# Testing_FixtureForAICarBoard.net
KiCad netlist of a schematic drawn in EAGLE
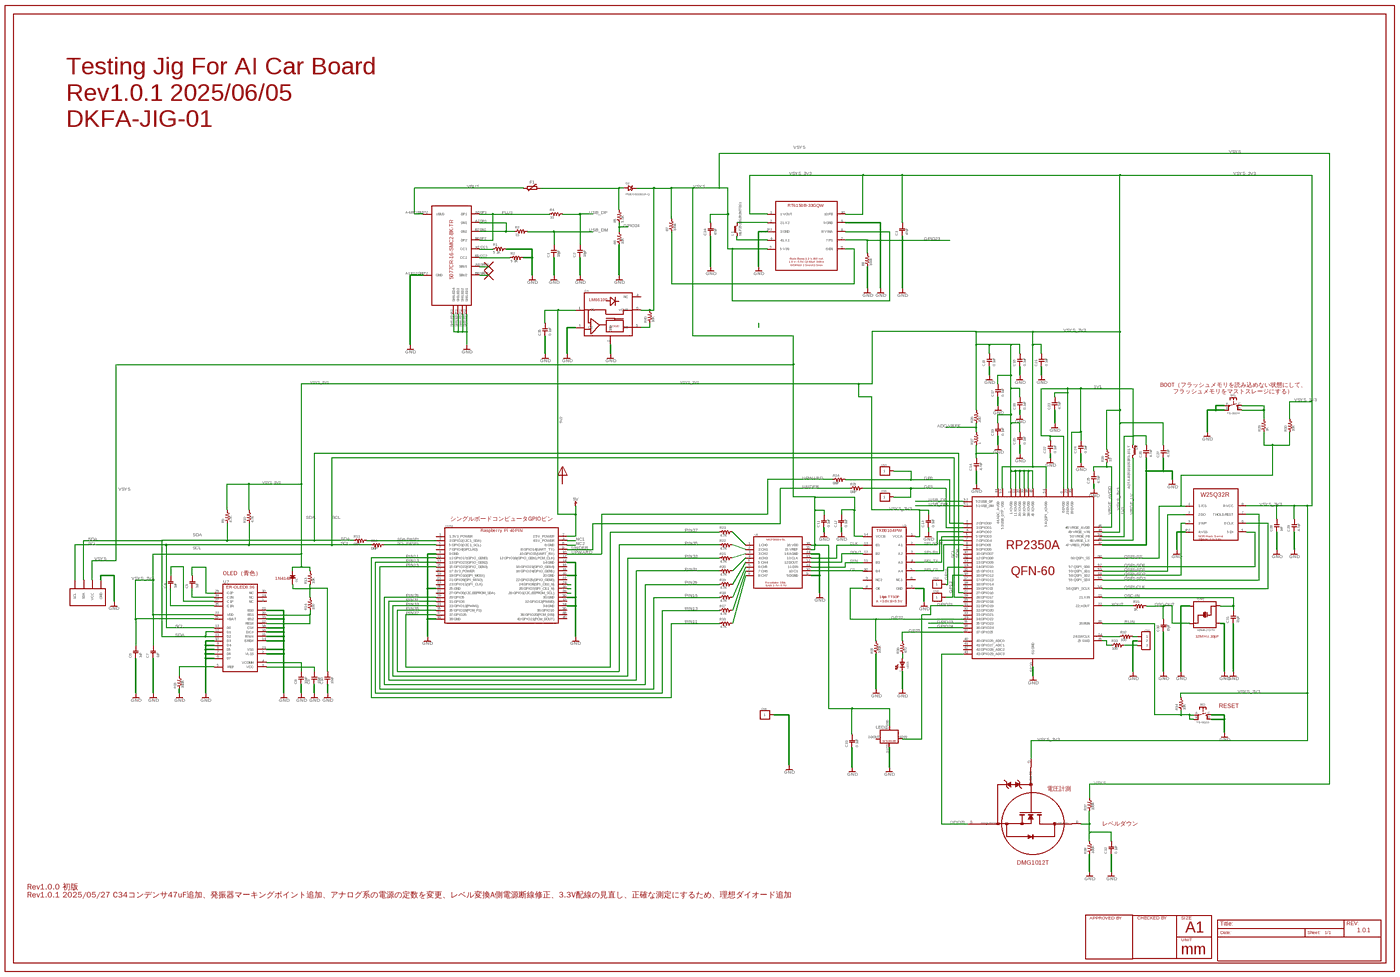
[diagram p0: schematic, sheet 1, overview]
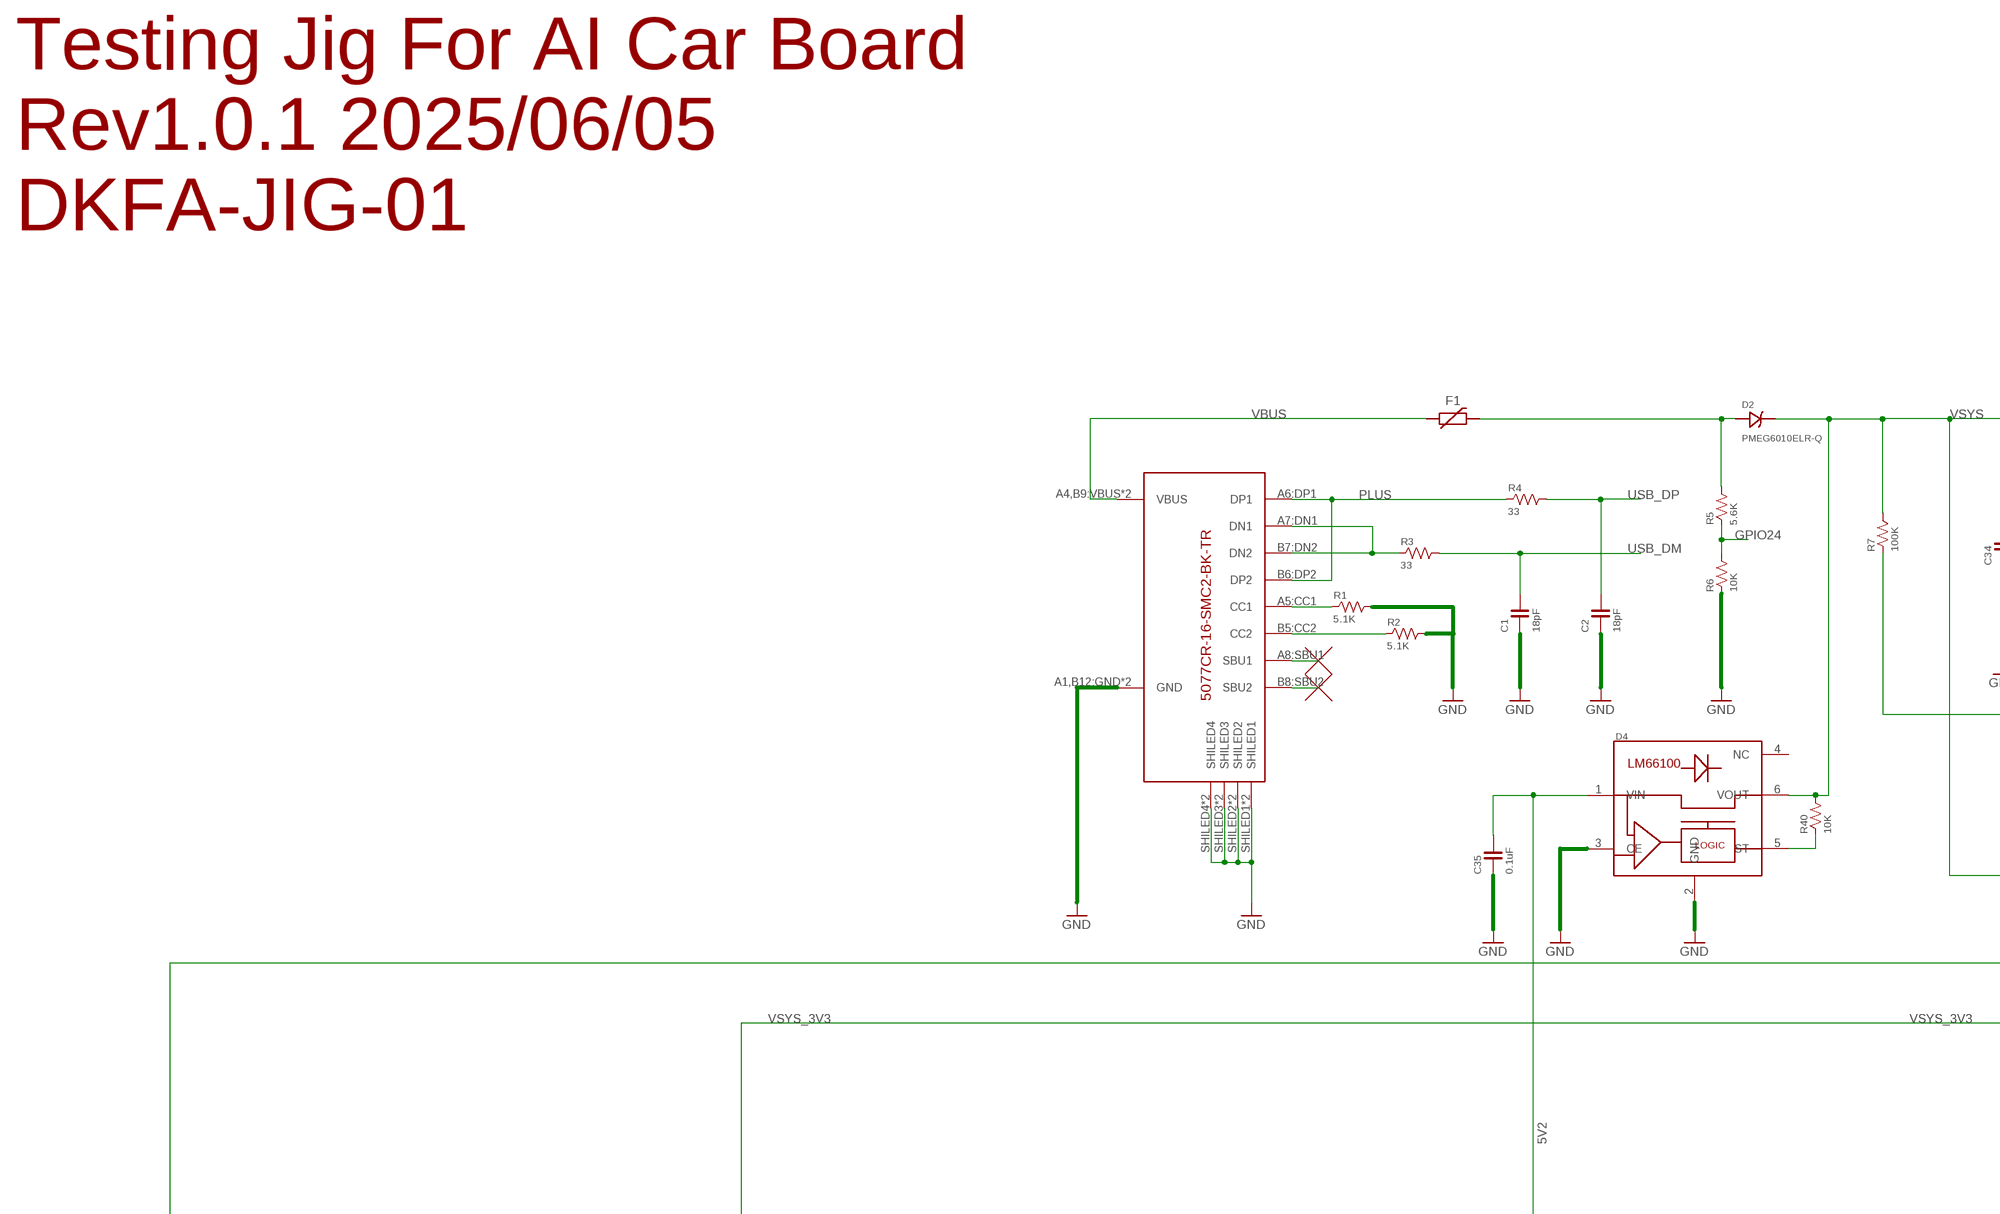
[diagram p1: schematic, sheet 1, part 1 of 4]
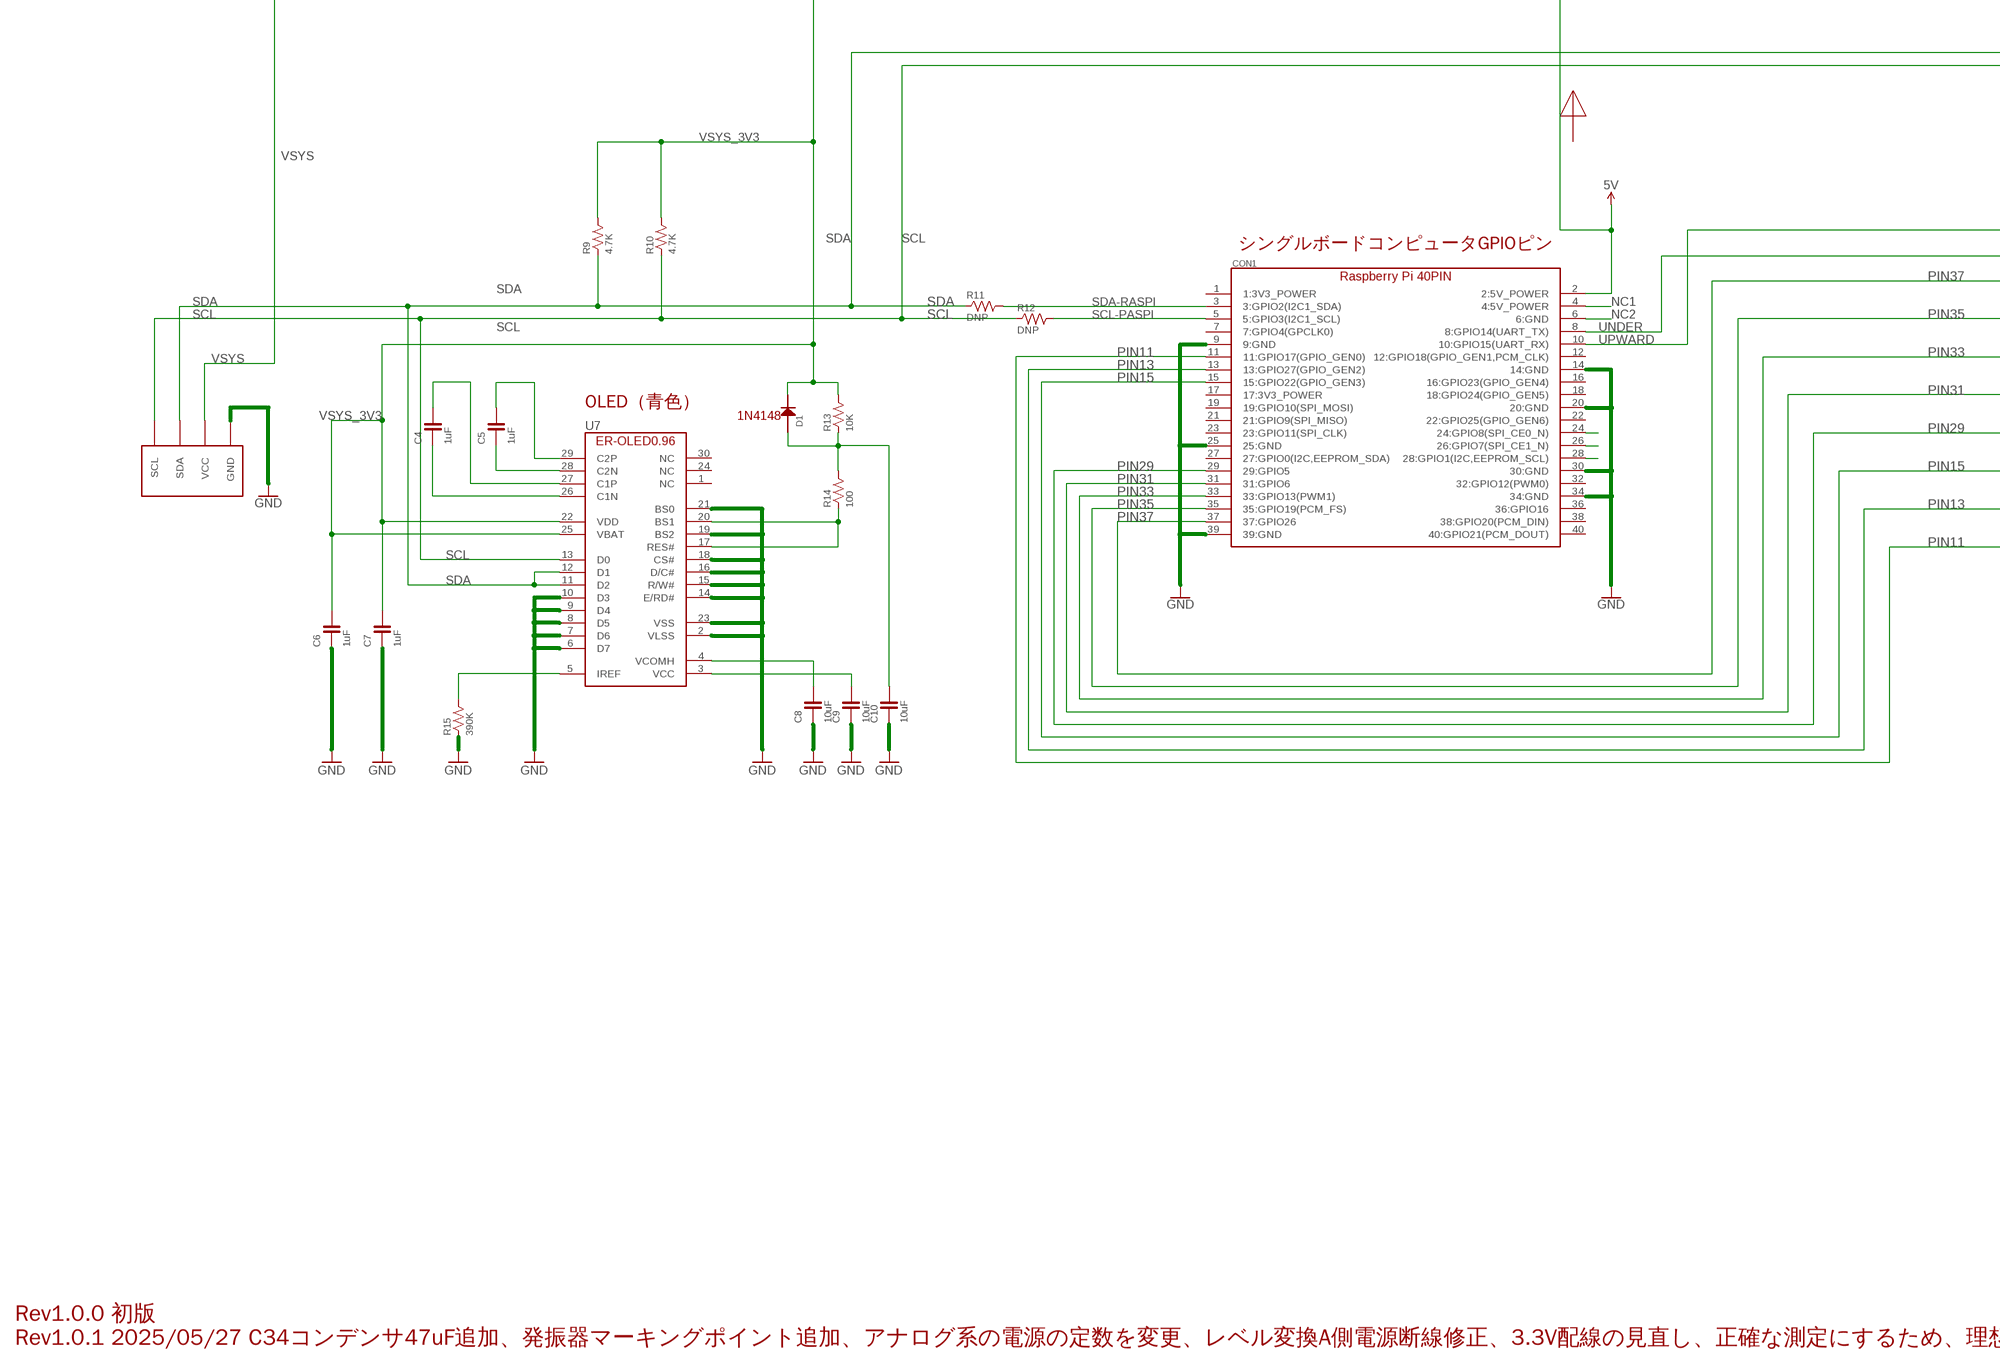
[diagram p2: schematic, sheet 1, part 2 of 4]
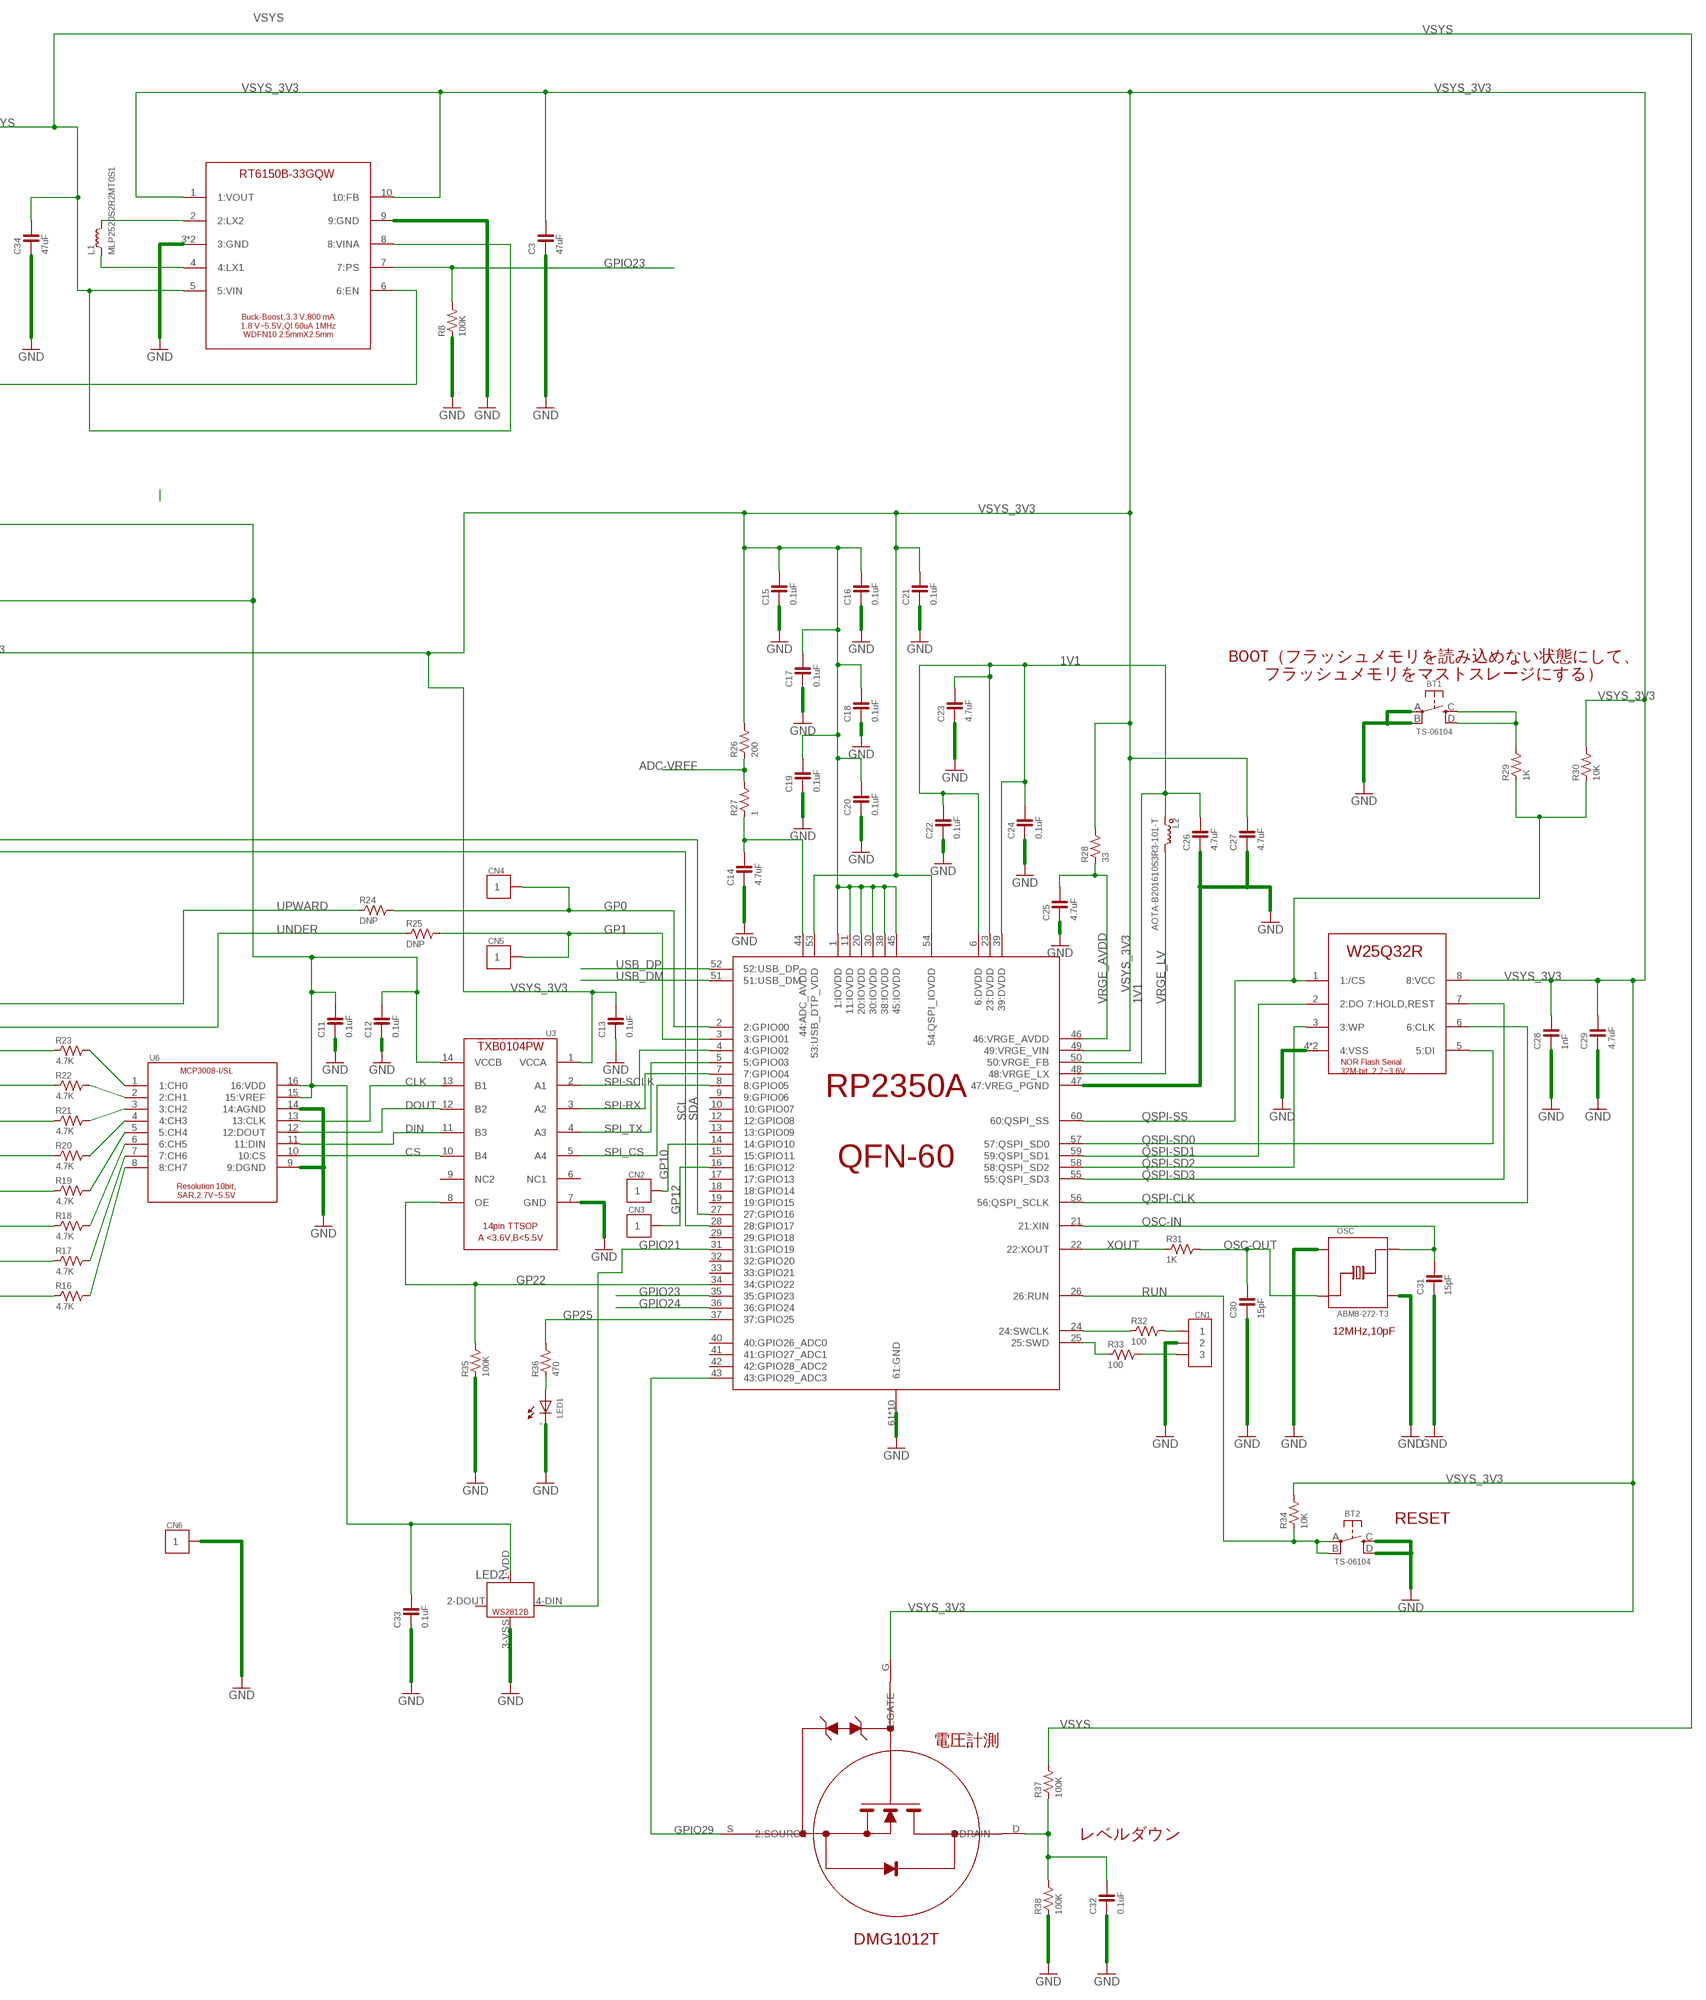
[diagram p3: schematic, sheet 1, part 3 of 4]
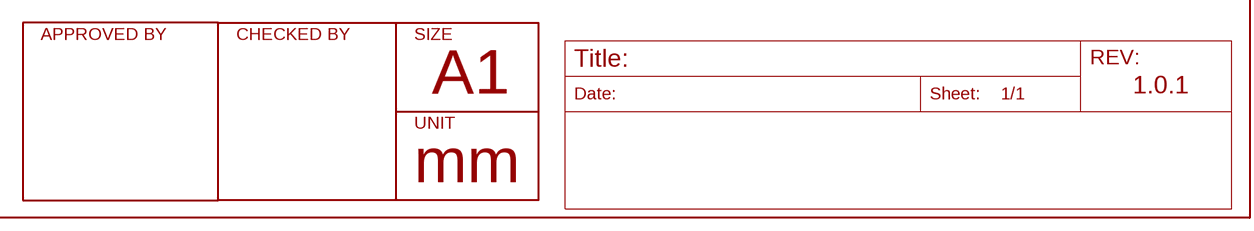
[diagram p4: schematic, sheet 1, part 4 of 4]

(export (version "E")
  (design (tool "Eeschema 10.0.6"))
  (components
    (comp (ref "BT1")
      (value "TS-06104")
      (footprint "eagle-import:TS-06104")
      (libsource (lib "eagle-import") (part "TS-06104"))
    )
    (comp (ref "BT2")
      (value "TS-06104")
      (footprint "eagle-import:TS-06104")
      (libsource (lib "eagle-import") (part "TS-06104"))
    )
    (comp (ref "C1")
      (value "18pF")
      (footprint "eagle-import:0603-BOTTOM")
      (fields (field (name "SPICEPREFIX") "C"))
      (libsource (lib "eagle-import") (part "CAPACITOR-0603-BOTTOM"))
    )
    (comp (ref "C2")
      (value "18pF")
      (footprint "eagle-import:0603-BOTTOM")
      (fields (field (name "SPICEPREFIX") "C"))
      (libsource (lib "eagle-import") (part "CAPACITOR-0603-BOTTOM"))
    )
    (comp (ref "C3")
      (value "47uF")
      (footprint "eagle-import:0603-BOTTOM")
      (fields (field (name "SPICEPREFIX") "C"))
      (libsource (lib "eagle-import") (part "CAPACITOR-0603-BOTTOM"))
    )
    (comp (ref "C4")
      (value "1uF")
      (footprint "eagle-import:0603-BOTTOM")
      (libsource (lib "eagle-import") (part "CAPACITOR-0603-BOTTOM"))
    )
    (comp (ref "C5")
      (value "1uF")
      (footprint "eagle-import:0603-BOTTOM")
      (libsource (lib "eagle-import") (part "CAPACITOR-0603-BOTTOM"))
    )
    (comp (ref "C6")
      (value "1uF")
      (footprint "eagle-import:0603-BOTTOM")
      (libsource (lib "eagle-import") (part "CAPACITOR-0603-BOTTOM"))
    )
    (comp (ref "C7")
      (value "1uF")
      (footprint "eagle-import:0603-BOTTOM")
      (libsource (lib "eagle-import") (part "CAPACITOR-0603-BOTTOM"))
    )
    (comp (ref "C8")
      (value "10uF")
      (footprint "eagle-import:0603-BOTTOM")
      (libsource (lib "eagle-import") (part "CAPACITOR-0603-BOTTOM"))
    )
    (comp (ref "C9")
      (value "10uF")
      (footprint "eagle-import:0603-BOTTOM")
      (libsource (lib "eagle-import") (part "CAPACITOR-0603-BOTTOM"))
    )
    (comp (ref "C10")
      (value "10uF")
      (footprint "eagle-import:0603-BOTTOM")
      (libsource (lib "eagle-import") (part "CAPACITOR-0603-BOTTOM"))
    )
    (comp (ref "C11")
      (value "0.1uF")
      (footprint "eagle-import:0603-BOTTOM")
      (fields (field (name "SPICEPREFIX") "C"))
      (libsource (lib "eagle-import") (part "CAPACITOR-0603-BOTTOM"))
    )
    (comp (ref "C12")
      (value "0.1uF")
      (footprint "eagle-import:0603-BOTTOM")
      (fields (field (name "SPICEPREFIX") "C"))
      (libsource (lib "eagle-import") (part "CAPACITOR-0603-BOTTOM"))
    )
    (comp (ref "C13")
      (value "0.1uF")
      (footprint "eagle-import:0603-BOTTOM")
      (fields (field (name "SPICEPREFIX") "C"))
      (libsource (lib "eagle-import") (part "CAPACITOR-0603-BOTTOM"))
    )
    (comp (ref "C14")
      (value "4.7uF")
      (footprint "eagle-import:0603-BOTTOM")
      (fields (field (name "SPICEPREFIX") "C"))
      (libsource (lib "eagle-import") (part "CAPACITOR-0603-BOTTOM"))
    )
    (comp (ref "C15")
      (value "0.1uF")
      (footprint "eagle-import:0603-BOTTOM")
      (fields (field (name "SPICEPREFIX") "C"))
      (libsource (lib "eagle-import") (part "CAPACITOR-0603-BOTTOM"))
    )
    (comp (ref "C16")
      (value "0.1uF")
      (footprint "eagle-import:0603-BOTTOM")
      (fields (field (name "SPICEPREFIX") "C"))
      (libsource (lib "eagle-import") (part "CAPACITOR-0603-BOTTOM"))
    )
    (comp (ref "C17")
      (value "0.1uF")
      (footprint "eagle-import:0603-BOTTOM")
      (fields (field (name "SPICEPREFIX") "C"))
      (libsource (lib "eagle-import") (part "CAPACITOR-0603-BOTTOM"))
    )
    (comp (ref "C18")
      (value "0.1uF")
      (footprint "eagle-import:0603-BOTTOM")
      (fields (field (name "SPICEPREFIX") "C"))
      (libsource (lib "eagle-import") (part "CAPACITOR-0603-BOTTOM"))
    )
    (comp (ref "C19")
      (value "0.1uF")
      (footprint "eagle-import:0603-BOTTOM")
      (fields (field (name "SPICEPREFIX") "C"))
      (libsource (lib "eagle-import") (part "CAPACITOR-0603-BOTTOM"))
    )
    (comp (ref "C20")
      (value "0.1uF")
      (footprint "eagle-import:0603-BOTTOM")
      (fields (field (name "SPICEPREFIX") "C"))
      (libsource (lib "eagle-import") (part "CAPACITOR-0603-BOTTOM"))
    )
    (comp (ref "C21")
      (value "0.1uF")
      (footprint "eagle-import:0603-BOTTOM")
      (fields (field (name "SPICEPREFIX") "C"))
      (libsource (lib "eagle-import") (part "CAPACITOR-0603-BOTTOM"))
    )
    (comp (ref "C22")
      (value "0.1uF")
      (footprint "eagle-import:0603-BOTTOM")
      (fields (field (name "SPICEPREFIX") "C"))
      (libsource (lib "eagle-import") (part "CAPACITOR-0603-BOTTOM"))
    )
    (comp (ref "C23")
      (value "4.7uF")
      (footprint "eagle-import:0603-BOTTOM")
      (fields (field (name "SPICEPREFIX") "C"))
      (libsource (lib "eagle-import") (part "CAPACITOR-0603-BOTTOM"))
    )
    (comp (ref "C24")
      (value "0.1uF")
      (footprint "eagle-import:0603-BOTTOM")
      (fields (field (name "SPICEPREFIX") "C"))
      (libsource (lib "eagle-import") (part "CAPACITOR-0603-BOTTOM"))
    )
    (comp (ref "C25")
      (value "4.7uF")
      (footprint "eagle-import:0603-BOTTOM")
      (fields (field (name "SPICEPREFIX") "C"))
      (libsource (lib "eagle-import") (part "CAPACITOR-0603-BOTTOM"))
    )
    (comp (ref "C26")
      (value "4.7uF")
      (footprint "eagle-import:0603-BOTTOM")
      (fields (field (name "SPICEPREFIX") "C"))
      (libsource (lib "eagle-import") (part "CAPACITOR-0603-BOTTOM"))
    )
    (comp (ref "C27")
      (value "4.7uF")
      (footprint "eagle-import:0603-BOTTOM")
      (fields (field (name "SPICEPREFIX") "C"))
      (libsource (lib "eagle-import") (part "CAPACITOR-0603-BOTTOM"))
    )
    (comp (ref "C28")
      (value "1nF")
      (footprint "eagle-import:0603-BOTTOM")
      (fields (field (name "SPICEPREFIX") "C"))
      (libsource (lib "eagle-import") (part "CAPACITOR-0603-BOTTOM"))
    )
    (comp (ref "C29")
      (value "4.7uF")
      (footprint "eagle-import:0603-BOTTOM")
      (fields (field (name "SPICEPREFIX") "C"))
      (libsource (lib "eagle-import") (part "CAPACITOR-0603-BOTTOM"))
    )
    (comp (ref "C30")
      (value "15pF")
      (footprint "eagle-import:0603-BOTTOM")
      (fields (field (name "SPICEPREFIX") "C"))
      (libsource (lib "eagle-import") (part "CAPACITOR-0603-BOTTOM"))
    )
    (comp (ref "C31")
      (value "15pF")
      (footprint "eagle-import:0603-BOTTOM")
      (fields (field (name "SPICEPREFIX") "C"))
      (libsource (lib "eagle-import") (part "CAPACITOR-0603-BOTTOM"))
    )
    (comp (ref "C32")
      (value "0.1uF")
      (footprint "eagle-import:0603-BOTTOM")
      (fields (field (name "SPICEPREFIX") "C"))
      (libsource (lib "eagle-import") (part "CAPACITOR-0603-BOTTOM"))
    )
    (comp (ref "C33")
      (value "0.1uF")
      (footprint "eagle-import:0603-BOTTOM")
      (fields (field (name "SPICEPREFIX") "C"))
      (libsource (lib "eagle-import") (part "CAPACITOR-0603-BOTTOM"))
    )
    (comp (ref "C34")
      (value "47uF")
      (footprint "eagle-import:0603-BOTTOM")
      (fields (field (name "SPICEPREFIX") "C"))
      (libsource (lib "eagle-import") (part "CAPACITOR-0603-BOTTOM"))
    )
    (comp (ref "C35")
      (value "0.1uF")
      (footprint "eagle-import:0603-BOTTOM")
      (fields (field (name "SPICEPREFIX") "C"))
      (libsource (lib "eagle-import") (part "CAPACITOR-0603-BOTTOM"))
    )
    (comp (ref "CN1")
      (value "PIN_1X3")
      (footprint "eagle-import:PIN_1X3")
      (libsource (lib "eagle-import") (part "PIN_1X3"))
    )
    (comp (ref "CN2")
      (value "PIN_1X1-SMALL")
      (footprint "eagle-import:PIN_1X1_SMALL")
      (libsource (lib "eagle-import") (part "PIN_1X1-SMALL"))
    )
    (comp (ref "CN3")
      (value "PIN_1X1-SMALL")
      (footprint "eagle-import:PIN_1X1_SMALL")
      (libsource (lib "eagle-import") (part "PIN_1X1-SMALL"))
    )
    (comp (ref "CN4")
      (value "PIN_1X1-SMALL")
      (footprint "eagle-import:PIN_1X1_SMALL")
      (libsource (lib "eagle-import") (part "PIN_1X1-SMALL"))
    )
    (comp (ref "CN5")
      (value "PIN_1X1-SMALL")
      (footprint "eagle-import:PIN_1X1_SMALL")
      (libsource (lib "eagle-import") (part "PIN_1X1-SMALL"))
    )
    (comp (ref "CN6")
      (value "PIN_1X1-SMALL")
      (footprint "eagle-import:PIN_1X1_SMALL")
      (libsource (lib "eagle-import") (part "PIN_1X1-SMALL"))
    )
    (comp (ref "CON1")
      (value "RASPBERRYPI_SHEILD")
      (footprint "eagle-import:RASPBERRY_PI_SHILED")
      (libsource (lib "eagle-import") (part "RASPBERRYPI_SHEILD"))
    )
    (comp (ref "CON2")
      (value "5077CR-16-SMC2-BK-TR")
      (footprint "eagle-import:5077CR-16-SMC2-BK-TR")
      (fields (field (name "SPICEPREFIX") "X"))
      (libsource (lib "eagle-import") (part "5077CR-16-SMC2-BK-TR"))
    )
    (comp (ref "CON3")
      (value "FABO_BRICK_I2C-S04B-PASK-2")
      (footprint "eagle-import:FABO_BRICK_I2C_S04B-PASK-2")
      (libsource (lib "eagle-import") (part "FABO_BRICK_I2C-S04B-PASK-2"))
    )
    (comp (ref "D1")
      (value "1N4148")
      (footprint "eagle-import:1N4148W")
      (libsource (lib "eagle-import") (part "1N4148"))
    )
    (comp (ref "D2")
      (value "PMEG6010ELR-Q")
      (footprint "eagle-import:SOD123W")
      (libsource (lib "eagle-import") (part "PMEG6010ELR-Q"))
    )
    (comp (ref "D4")
      (value "LM66100")
      (footprint "eagle-import:SC-70")
      (libsource (lib "eagle-import") (part "LM66100"))
    )
    (comp (ref "F1")
      (value "POLYSWITCH1206")
      (footprint "eagle-import:1206")
      (libsource (lib "eagle-import") (part "POLYSWITCH1206"))
    )
    (comp (ref "L1")
      (value "MLP2520S2R2MT0S1")
      (footprint "eagle-import:1008(2520MM)")
      (libsource (lib "eagle-import") (part "MLP2520S2R2MT0S1"))
    )
    (comp (ref "L2")
      (value "AOTA-B201610S3R3-101-T")
      (footprint "eagle-import:0806(2016MM)")
      (libsource (lib "eagle-import") (part "AOTA-B201610S3R3-101-T"))
    )
    (comp (ref "LED1")
      (value "LED-0603")
      (footprint "eagle-import:0603")
      (libsource (lib "eagle-import") (part "LED-0603"))
    )
    (comp (ref "LED2")
      (value "WS2812B_NARROW")
      (footprint "eagle-import:WS2812B_NARROW")
      (libsource (lib "eagle-import") (part "WS2812B_NARROW"))
    )
    (comp (ref "OSC")
      (value "ABM8-272-T3")
      (footprint "eagle-import:ABM8-272-T3")
      (libsource (lib "eagle-import") (part "ABM8-272-T3"))
    )
    (comp (ref "R1")
      (value "5.1K")
      (footprint "eagle-import:0603-BOTTOM")
      (fields (field (name "SPICEPREFIX") "R"))
      (libsource (lib "eagle-import") (part "RESISTOR-0603-BOTTOM"))
    )
    (comp (ref "R2")
      (value "5.1K")
      (footprint "eagle-import:0603-BOTTOM")
      (fields (field (name "SPICEPREFIX") "R"))
      (libsource (lib "eagle-import") (part "RESISTOR-0603-BOTTOM"))
    )
    (comp (ref "R3")
      (value "33")
      (footprint "eagle-import:0603-BOTTOM")
      (fields (field (name "SPICEPREFIX") "R"))
      (libsource (lib "eagle-import") (part "RESISTOR-0603-BOTTOM"))
    )
    (comp (ref "R4")
      (value "33")
      (footprint "eagle-import:0603-BOTTOM")
      (fields (field (name "SPICEPREFIX") "R"))
      (libsource (lib "eagle-import") (part "RESISTOR-0603-BOTTOM"))
    )
    (comp (ref "R5")
      (value "5.6K")
      (footprint "eagle-import:0603")
      (libsource (lib "eagle-import") (part "RESISTOR-0603"))
    )
    (comp (ref "R6")
      (value "10K")
      (footprint "eagle-import:0603")
      (libsource (lib "eagle-import") (part "RESISTOR-0603"))
    )
    (comp (ref "R7")
      (value "100K")
      (footprint "eagle-import:0603-BOTTOM")
      (fields (field (name "SPICEPREFIX") "R"))
      (libsource (lib "eagle-import") (part "RESISTOR-0603-BOTTOM"))
    )
    (comp (ref "R8")
      (value "100K")
      (footprint "eagle-import:0603-BOTTOM")
      (fields (field (name "SPICEPREFIX") "R"))
      (libsource (lib "eagle-import") (part "RESISTOR-0603-BOTTOM"))
    )
    (comp (ref "R9")
      (value "4.7K")
      (footprint "eagle-import:0603-BOTTOM")
      (libsource (lib "eagle-import") (part "RESISTOR-0603-BOTTOM"))
    )
    (comp (ref "R10")
      (value "4.7K")
      (footprint "eagle-import:0603-BOTTOM")
      (libsource (lib "eagle-import") (part "RESISTOR-0603-BOTTOM"))
    )
    (comp (ref "R11")
      (value "DNP")
      (footprint "eagle-import:0603-BOTTOM")
      (fields (field (name "SPICEPREFIX") "R"))
      (libsource (lib "eagle-import") (part "RESISTOR-0603-BOTTOM"))
    )
    (comp (ref "R12")
      (value "DNP")
      (footprint "eagle-import:0603-BOTTOM")
      (fields (field (name "SPICEPREFIX") "R"))
      (libsource (lib "eagle-import") (part "RESISTOR-0603-BOTTOM"))
    )
    (comp (ref "R13")
      (value "10K")
      (footprint "eagle-import:0603-BOTTOM")
      (libsource (lib "eagle-import") (part "RESISTOR-0603-BOTTOM"))
    )
    (comp (ref "R14")
      (value "100")
      (footprint "eagle-import:0603-BOTTOM")
      (libsource (lib "eagle-import") (part "RESISTOR-0603-BOTTOM"))
    )
    (comp (ref "R15")
      (value "390K")
      (footprint "eagle-import:0603-BOTTOM")
      (libsource (lib "eagle-import") (part "RESISTOR-0603-BOTTOM"))
    )
    (comp (ref "R16")
      (value "4.7K")
      (footprint "eagle-import:0603-BOTTOM")
      (fields (field (name "SPICEPREFIX") "R"))
      (libsource (lib "eagle-import") (part "RESISTOR-0603-BOTTOM"))
    )
    (comp (ref "R17")
      (value "4.7K")
      (footprint "eagle-import:0603-BOTTOM")
      (fields (field (name "SPICEPREFIX") "R"))
      (libsource (lib "eagle-import") (part "RESISTOR-0603-BOTTOM"))
    )
    (comp (ref "R18")
      (value "4.7K")
      (footprint "eagle-import:0603-BOTTOM")
      (fields (field (name "SPICEPREFIX") "R"))
      (libsource (lib "eagle-import") (part "RESISTOR-0603-BOTTOM"))
    )
    (comp (ref "R19")
      (value "4.7K")
      (footprint "eagle-import:0603-BOTTOM")
      (fields (field (name "SPICEPREFIX") "R"))
      (libsource (lib "eagle-import") (part "RESISTOR-0603-BOTTOM"))
    )
    (comp (ref "R20")
      (value "4.7K")
      (footprint "eagle-import:0603-BOTTOM")
      (fields (field (name "SPICEPREFIX") "R"))
      (libsource (lib "eagle-import") (part "RESISTOR-0603-BOTTOM"))
    )
    (comp (ref "R21")
      (value "4.7K")
      (footprint "eagle-import:0603-BOTTOM")
      (fields (field (name "SPICEPREFIX") "R"))
      (libsource (lib "eagle-import") (part "RESISTOR-0603-BOTTOM"))
    )
    (comp (ref "R22")
      (value "4.7K")
      (footprint "eagle-import:0603-BOTTOM")
      (fields (field (name "SPICEPREFIX") "R"))
      (libsource (lib "eagle-import") (part "RESISTOR-0603-BOTTOM"))
    )
    (comp (ref "R23")
      (value "4.7K")
      (footprint "eagle-import:0603-BOTTOM")
      (fields (field (name "SPICEPREFIX") "R"))
      (libsource (lib "eagle-import") (part "RESISTOR-0603-BOTTOM"))
    )
    (comp (ref "R24")
      (value "DNP")
      (footprint "eagle-import:0603-BOTTOM")
      (fields (field (name "SPICEPREFIX") "R"))
      (libsource (lib "eagle-import") (part "RESISTOR-0603-BOTTOM"))
    )
    (comp (ref "R25")
      (value "DNP")
      (footprint "eagle-import:0603-BOTTOM")
      (fields (field (name "SPICEPREFIX") "R"))
      (libsource (lib "eagle-import") (part "RESISTOR-0603-BOTTOM"))
    )
    (comp (ref "R26")
      (value "200")
      (footprint "eagle-import:0603-BOTTOM")
      (fields (field (name "SPICEPREFIX") "R"))
      (libsource (lib "eagle-import") (part "RESISTOR-0603-BOTTOM"))
    )
    (comp (ref "R27")
      (value "1")
      (footprint "eagle-import:0603-BOTTOM")
      (fields (field (name "SPICEPREFIX") "R"))
      (libsource (lib "eagle-import") (part "RESISTOR-0603-BOTTOM"))
    )
    (comp (ref "R28")
      (value "33")
      (footprint "eagle-import:0603-BOTTOM")
      (fields (field (name "SPICEPREFIX") "R"))
      (libsource (lib "eagle-import") (part "RESISTOR-0603-BOTTOM"))
    )
    (comp (ref "R29")
      (value "1K")
      (footprint "eagle-import:0603-BOTTOM")
      (fields (field (name "SPICEPREFIX") "R"))
      (libsource (lib "eagle-import") (part "RESISTOR-0603-BOTTOM"))
    )
    (comp (ref "R30")
      (value "10K")
      (footprint "eagle-import:0603-BOTTOM")
      (fields (field (name "SPICEPREFIX") "R"))
      (libsource (lib "eagle-import") (part "RESISTOR-0603-BOTTOM"))
    )
    (comp (ref "R31")
      (value "1K")
      (footprint "eagle-import:0603-BOTTOM")
      (libsource (lib "eagle-import") (part "RESISTOR-0603-BOTTOM"))
    )
    (comp (ref "R32")
      (value "100")
      (footprint "eagle-import:0603-BOTTOM")
      (libsource (lib "eagle-import") (part "RESISTOR-0603-BOTTOM"))
    )
    (comp (ref "R33")
      (value "100")
      (footprint "eagle-import:0603-BOTTOM")
      (libsource (lib "eagle-import") (part "RESISTOR-0603-BOTTOM"))
    )
    (comp (ref "R34")
      (value "10K")
      (footprint "eagle-import:0603-BOTTOM")
      (fields (field (name "SPICEPREFIX") "R"))
      (libsource (lib "eagle-import") (part "RESISTOR-0603-BOTTOM"))
    )
    (comp (ref "R35")
      (value "100K")
      (footprint "eagle-import:0603-BOTTOM")
      (fields (field (name "SPICEPREFIX") "R"))
      (libsource (lib "eagle-import") (part "RESISTOR-0603-BOTTOM"))
    )
    (comp (ref "R36")
      (value "470")
      (footprint "eagle-import:0603-BOTTOM")
      (fields (field (name "SPICEPREFIX") "R"))
      (libsource (lib "eagle-import") (part "RESISTOR-0603-BOTTOM"))
    )
    (comp (ref "R37")
      (value "100K")
      (footprint "eagle-import:0603")
      (libsource (lib "eagle-import") (part "RESISTOR-0603"))
    )
    (comp (ref "R38")
      (value "100K")
      (footprint "eagle-import:0603")
      (libsource (lib "eagle-import") (part "RESISTOR-0603"))
    )
    (comp (ref "R40")
      (value "10K")
      (footprint "eagle-import:0603")
      (libsource (lib "eagle-import") (part "RESISTOR-0603"))
    )
    (comp (ref "U1")
      (value "RP2350A")
      (footprint "eagle-import:QFN60")
      (libsource (lib "eagle-import") (part "RP2350A"))
    )
    (comp (ref "U2")
      (value "W25Q32RVXHJQ")
      (footprint "eagle-import:XSON8")
      (libsource (lib "eagle-import") (part "W25Q32RVXHJQ"))
    )
    (comp (ref "U3")
      (value "TXB0104")
      (footprint "eagle-import:TSSOP-14")
      (libsource (lib "eagle-import") (part "TXB0104"))
    )
    (comp (ref "U4")
      (value "RT6150B-33GQW")
      (footprint "eagle-import:WDFN-10L_2.5X2.5MM")
      (libsource (lib "eagle-import") (part "RT6150B-33GQW"))
    )
    (comp (ref "U5")
      (value "DMG1012T")
      (footprint "eagle-import:SOT-523")
      (libsource (lib "eagle-import") (part "DMG1012T"))
    )
    (comp (ref "U6")
      (value "MCP3008")
      (footprint "eagle-import:SOIC-16")
      (libsource (lib "eagle-import") (part "MCP3008"))
    )
    (comp (ref "U7")
      (value "ER-OLED0.96-1ER-CON30HT-1_REV2")
      (footprint "eagle-import:ER-CON30HT-1_REV2")
      (libsource (lib "eagle-import") (part "ER-OLED0.96-1ER-CON30HT-1_REV2"))
    )
  )
  (nets
    (net (code "1") (name "/1:3V3_POWER") (class "Default")
      (node (ref "CON1") (pin "1") (pinfunction "1:3V3_POWER_1") (pintype "power_in"))
    )
    (net (code "2") (name "/1V1") (class "Default")
      (node (ref "C22") (pin "2") (pinfunction "2_2") (pintype "passive"))
      (node (ref "C23") (pin "2") (pinfunction "2_2") (pintype "passive"))
      (node (ref "C24") (pin "2") (pinfunction "2_2") (pintype "passive"))
      (node (ref "C26") (pin "2") (pinfunction "2_2") (pintype "passive"))
      (node (ref "L2") (pin "2") (pinfunction "1_2") (pintype "passive"))
      (node (ref "U1") (pin "23") (pinfunction "23:DVDD_23") (pintype "power_in"))
      (node (ref "U1") (pin "39") (pinfunction "39:DVDD_39") (pintype "power_in"))
      (node (ref "U1") (pin "50") (pinfunction "50:VRGE_FB_50") (pintype "input"))
      (node (ref "U1") (pin "6") (pinfunction "6:DVDD_6") (pintype "power_in"))
    )
    (net (code "3") (name "/17:3V3_POWER") (class "Default")
      (node (ref "CON1") (pin "17") (pinfunction "17:3V3_POWER_17") (pintype "power_in"))
    )
    (net (code "4") (name "/ADC-VREF") (class "Default")
      (node (ref "R26") (pin "1") (pinfunction "1_1") (pintype "bidirectional"))
      (node (ref "R27") (pin "2") (pinfunction "2_2") (pintype "bidirectional"))
    )
    (net (code "5") (name "/CLK") (class "Default")
      (node (ref "U3") (pin "13") (pinfunction "B1_13") (pintype "bidirectional"))
      (node (ref "U6") (pin "13") (pinfunction "13:CLK_13") (pintype "input"))
    )
    (net (code "6") (name "/CS") (class "Default")
      (node (ref "U3") (pin "10") (pinfunction "B4_10") (pintype "bidirectional"))
      (node (ref "U6") (pin "10") (pinfunction "10:CS_10") (pintype "input"))
    )
    (net (code "7") (name "/DIN") (class "Default")
      (node (ref "U3") (pin "11") (pinfunction "B3_11") (pintype "bidirectional"))
      (node (ref "U6") (pin "11") (pinfunction "11:DIN_11") (pintype "input"))
    )
    (net (code "8") (name "/DOUT") (class "Default")
      (node (ref "U3") (pin "12") (pinfunction "B2_12") (pintype "bidirectional"))
      (node (ref "U6") (pin "12") (pinfunction "12:DOUT_12") (pintype "output"))
    )
    (net (code "9") (name "/GP0") (class "Default")
      (node (ref "CN4") (pin "1") (pinfunction "1_1") (pintype "bidirectional"))
      (node (ref "R24") (pin "2") (pinfunction "2_2") (pintype "bidirectional"))
      (node (ref "U1") (pin "2") (pinfunction "2:GPIO00_2") (pintype "bidirectional"))
    )
    (net (code "10") (name "/GP1") (class "Default")
      (node (ref "CN5") (pin "1") (pinfunction "1_1") (pintype "bidirectional"))
      (node (ref "R25") (pin "2") (pinfunction "2_2") (pintype "bidirectional"))
      (node (ref "U1") (pin "3") (pinfunction "3:GPIO01_3") (pintype "bidirectional"))
    )
    (net (code "11") (name "/GP10") (class "Default")
      (node (ref "CN2") (pin "1") (pinfunction "1_1") (pintype "bidirectional"))
      (node (ref "U1") (pin "14") (pinfunction "14:GPIO10_14") (pintype "bidirectional"))
    )
    (net (code "12") (name "/GP12") (class "Default")
      (node (ref "CN3") (pin "1") (pinfunction "1_1") (pintype "bidirectional"))
      (node (ref "U1") (pin "16") (pinfunction "16:GPIO12_16") (pintype "bidirectional"))
    )
    (net (code "13") (name "/GP22") (class "Default")
      (node (ref "R35") (pin "2") (pinfunction "2_2") (pintype "bidirectional"))
      (node (ref "U1") (pin "34") (pinfunction "34:GPIO22_34") (pintype "bidirectional"))
      (node (ref "U3") (pin "8") (pinfunction "OE_8") (pintype "input"))
    )
    (net (code "14") (name "/GP25") (class "Default")
      (node (ref "R36") (pin "2") (pinfunction "2_2") (pintype "bidirectional"))
      (node (ref "U1") (pin "37") (pinfunction "37:GPIO25_37") (pintype "bidirectional"))
    )
    (net (code "15") (name "/GPIO21") (class "Default")
      (node (ref "LED2") (pin "4-DIN") (pinfunction "DIN_4-DIN") (pintype "bidirectional"))
      (node (ref "U1") (pin "31") (pinfunction "31:GPIO19_31") (pintype "bidirectional"))
    )
    (net (code "16") (name "/GPIO23") (class "Default")
      (node (ref "R8") (pin "2") (pinfunction "2_2") (pintype "bidirectional"))
      (node (ref "U1") (pin "35") (pinfunction "35:GPIO23_35") (pintype "bidirectional"))
      (node (ref "U4") (pin "7") (pinfunction "7:PS_7") (pintype "input"))
    )
    (net (code "17") (name "/GPIO24") (class "Default")
      (node (ref "R5") (pin "1") (pinfunction "1_1") (pintype "bidirectional"))
      (node (ref "R6") (pin "2") (pinfunction "2_2") (pintype "bidirectional"))
      (node (ref "U1") (pin "36") (pinfunction "36:GPIO24_36") (pintype "bidirectional"))
    )
    (net (code "18") (name "/GPIO29") (class "Default")
      (node (ref "U1") (pin "43") (pinfunction "43:GPIO29_ADC3_43") (pintype "bidirectional"))
      (node (ref "U5") (pin "S") (pinfunction "2:SOURCE_S") (pintype "passive"))
    )
    (net (code "19") (name "/NC1") (class "Default")
      (node (ref "CON1") (pin "4") (pinfunction "4:5V_POWER_4") (pintype "power_in"))
    )
    (net (code "20") (name "/NC2") (class "Default")
      (node (ref "CON1") (pin "6") (pinfunction "6:GND_6") (pintype "power_in"))
    )
    (net (code "21") (name "/OSC-IN") (class "Default")
      (node (ref "C31") (pin "2") (pinfunction "2_2") (pintype "passive"))
      (node (ref "OSC") (pin "3") (pinfunction "#3_3") (pintype "passive"))
      (node (ref "U1") (pin "21") (pinfunction "21:XIN_21") (pintype "input"))
    )
    (net (code "22") (name "/OSC-OUT") (class "Default")
      (node (ref "C30") (pin "2") (pinfunction "2_2") (pintype "passive"))
      (node (ref "OSC") (pin "1") (pinfunction "#1_1") (pintype "passive"))
      (node (ref "R31") (pin "2") (pinfunction "2_2") (pintype "bidirectional"))
    )
    (net (code "23") (name "/PIN11") (class "Default")
      (node (ref "CON1") (pin "11") (pinfunction "11:GPIO17(GPIO_GEN0)_11") (pintype "bidirectional"))
      (node (ref "R16") (pin "1") (pinfunction "1_1") (pintype "bidirectional"))
    )
    (net (code "24") (name "/PIN13") (class "Default")
      (node (ref "CON1") (pin "13") (pinfunction "13:GPIO27(GPIO_GEN2)_13") (pintype "bidirectional"))
      (node (ref "R17") (pin "1") (pinfunction "1_1") (pintype "bidirectional"))
    )
    (net (code "25") (name "/PIN15") (class "Default")
      (node (ref "CON1") (pin "15") (pinfunction "15:GPIO22(GPIO_GEN3)_15") (pintype "bidirectional"))
      (node (ref "R18") (pin "1") (pinfunction "1_1") (pintype "bidirectional"))
    )
    (net (code "26") (name "/PIN29") (class "Default")
      (node (ref "CON1") (pin "29") (pinfunction "29:GPIO5_29") (pintype "bidirectional"))
      (node (ref "R19") (pin "1") (pinfunction "1_1") (pintype "bidirectional"))
    )
    (net (code "27") (name "/PIN31") (class "Default")
      (node (ref "CON1") (pin "31") (pinfunction "31:GPIO6_31") (pintype "bidirectional"))
      (node (ref "R20") (pin "1") (pinfunction "1_1") (pintype "bidirectional"))
    )
    (net (code "28") (name "/PIN33") (class "Default")
      (node (ref "CON1") (pin "33") (pinfunction "33:GPIO13(PWM1)_33") (pintype "bidirectional"))
      (node (ref "R21") (pin "1") (pinfunction "1_1") (pintype "bidirectional"))
    )
    (net (code "29") (name "/PIN35") (class "Default")
      (node (ref "CON1") (pin "35") (pinfunction "35:GPIO19(PCM_FS)_35") (pintype "bidirectional"))
      (node (ref "R22") (pin "1") (pinfunction "1_1") (pintype "bidirectional"))
    )
    (net (code "30") (name "/PIN37") (class "Default")
      (node (ref "CON1") (pin "37") (pinfunction "37:GPIO26_37") (pintype "bidirectional"))
      (node (ref "R23") (pin "1") (pinfunction "1_1") (pintype "bidirectional"))
    )
    (net (code "31") (name "/PLUS") (class "Default")
      (node (ref "CON2") (pin "A6:DP1") (pinfunction "DP1_A6:DP1") (pintype "bidirectional"))
      (node (ref "CON2") (pin "B6:DP2") (pinfunction "DP2_B6:DP2") (pintype "bidirectional"))
      (node (ref "R4") (pin "1") (pinfunction "1_1") (pintype "bidirectional"))
    )
    (net (code "32") (name "/QSPI-CLK") (class "Default")
      (node (ref "U1") (pin "56") (pinfunction "56:QSPI_SCLK_56") (pintype "output"))
      (node (ref "U2") (pin "6") (pinfunction "6:CLK_6") (pintype "input"))
    )
    (net (code "33") (name "/QSPI-SD0") (class "Default")
      (node (ref "U1") (pin "57") (pinfunction "57:QSPI_SD0_57") (pintype "bidirectional"))
      (node (ref "U2") (pin "5") (pinfunction "5:DI_5") (pintype "bidirectional"))
    )
    (net (code "34") (name "/QSPI-SD1") (class "Default")
      (node (ref "U1") (pin "59") (pinfunction "59:QSPI_SD1_59") (pintype "bidirectional"))
      (node (ref "U2") (pin "2") (pinfunction "2:DO_2") (pintype "output"))
    )
    (net (code "35") (name "/QSPI-SD2") (class "Default")
      (node (ref "U1") (pin "58") (pinfunction "58:QSPI_SD2_58") (pintype "bidirectional"))
      (node (ref "U2") (pin "3") (pinfunction "3:WP_3") (pintype "bidirectional"))
    )
    (net (code "36") (name "/QSPI-SD3") (class "Default")
      (node (ref "U1") (pin "55") (pinfunction "55:QSPI_SD3_55") (pintype "bidirectional"))
      (node (ref "U2") (pin "7") (pinfunction "7:HOLD,REST_7") (pintype "bidirectional"))
    )
    (net (code "37") (name "/QSPI-SS") (class "Default")
      (node (ref "R29") (pin "1") (pinfunction "1_1") (pintype "bidirectional"))
      (node (ref "R30") (pin "1") (pinfunction "1_1") (pintype "bidirectional"))
      (node (ref "U1") (pin "60") (pinfunction "60:QSPI_SS_60") (pintype "output"))
      (node (ref "U2") (pin "1") (pinfunction "1:/CS_1") (pintype "input"))
    )
    (net (code "38") (name "/RUN") (class "Default")
      (node (ref "BT2") (pin "A") (pinfunction "A_A") (pintype "passive"))
      (node (ref "BT2") (pin "B") (pinfunction "B_B") (pintype "passive"))
      (node (ref "R34") (pin "1") (pinfunction "1_1") (pintype "bidirectional"))
      (node (ref "U1") (pin "26") (pinfunction "26:RUN_26") (pintype "input"))
    )
    (net (code "39") (name "/SCL") (class "Default")
      (node (ref "CON3") (pin "SCL") (pinfunction "SCL_SCL") (pintype "bidirectional"))
      (node (ref "R10") (pin "1") (pinfunction "1_1") (pintype "bidirectional"))
      (node (ref "R12") (pin "1") (pinfunction "1_1") (pintype "bidirectional"))
      (node (ref "U1") (pin "28") (pinfunction "28:GPIO17_28") (pintype "bidirectional"))
      (node (ref "U7") (pin "13") (pinfunction "D0_13") (pintype "bidirectional"))
    )
    (net (code "40") (name "/SCL-PASPI") (class "Default")
      (node (ref "CON1") (pin "5") (pinfunction "5:GPIO3(I2C1_SCL)_5") (pintype "bidirectional"))
      (node (ref "R12") (pin "2") (pinfunction "2_2") (pintype "bidirectional"))
    )
    (net (code "41") (name "/SDA") (class "Default")
      (node (ref "CON3") (pin "SDA") (pinfunction "SDA_SDA") (pintype "bidirectional"))
      (node (ref "R11") (pin "1") (pinfunction "1_1") (pintype "bidirectional"))
      (node (ref "R9") (pin "1") (pinfunction "1_1") (pintype "bidirectional"))
      (node (ref "U1") (pin "27") (pinfunction "27:GPIO16_27") (pintype "bidirectional"))
      (node (ref "U7") (pin "11") (pinfunction "D2_11") (pintype "bidirectional"))
      (node (ref "U7") (pin "12") (pinfunction "D1_12") (pintype "bidirectional"))
    )
    (net (code "42") (name "/SDA-RASPI") (class "Default")
      (node (ref "CON1") (pin "3") (pinfunction "3:GPIO2(I2C1_SDA)_3") (pintype "bidirectional"))
      (node (ref "R11") (pin "2") (pinfunction "2_2") (pintype "bidirectional"))
    )
    (net (code "43") (name "/SPI-RX") (class "Default")
      (node (ref "U1") (pin "7") (pinfunction "7:GPIO04_7") (pintype "bidirectional"))
      (node (ref "U3") (pin "3") (pinfunction "A2_3") (pintype "bidirectional"))
    )
    (net (code "44") (name "/SPI-SCLK") (class "Default")
      (node (ref "U1") (pin "4") (pinfunction "4:GPIO02_4") (pintype "bidirectional"))
      (node (ref "U3") (pin "2") (pinfunction "A1_2") (pintype "bidirectional"))
    )
    (net (code "45") (name "/SPI_CS") (class "Default")
      (node (ref "U1") (pin "8") (pinfunction "8:GPIO05_8") (pintype "bidirectional"))
      (node (ref "U3") (pin "5") (pinfunction "A4_5") (pintype "bidirectional"))
    )
    (net (code "46") (name "/SPI_TX") (class "Default")
      (node (ref "U1") (pin "5") (pinfunction "5:GPIO03_5") (pintype "bidirectional"))
      (node (ref "U3") (pin "4") (pinfunction "A3_4") (pintype "bidirectional"))
    )
    (net (code "47") (name "/UNDER") (class "Default")
      (node (ref "CON1") (pin "8") (pinfunction "8:GPIO14(UART_TX)_8") (pintype "bidirectional"))
      (node (ref "R25") (pin "1") (pinfunction "1_1") (pintype "bidirectional"))
    )
    (net (code "48") (name "/UPWARD") (class "Default")
      (node (ref "CON1") (pin "10") (pinfunction "10:GPIO15(UART_RX)_10") (pintype "bidirectional"))
      (node (ref "R24") (pin "1") (pinfunction "1_1") (pintype "bidirectional"))
    )
    (net (code "49") (name "/USB_DM") (class "Default")
      (node (ref "C1") (pin "2") (pinfunction "2_2") (pintype "passive"))
      (node (ref "R3") (pin "2") (pinfunction "2_2") (pintype "bidirectional"))
      (node (ref "U1") (pin "51") (pinfunction "51:USB_DM_51") (pintype "bidirectional"))
    )
    (net (code "50") (name "/USB_DP") (class "Default")
      (node (ref "C2") (pin "2") (pinfunction "2_2") (pintype "passive"))
      (node (ref "R4") (pin "2") (pinfunction "2_2") (pintype "bidirectional"))
      (node (ref "U1") (pin "52") (pinfunction "52:USB_DP_52") (pintype "bidirectional"))
    )
    (net (code "51") (name "/VBUS") (class "Default")
      (node (ref "CON2") (pin "A4,B9:VBUS") (pinfunction "VBUS_A4,B9:VBUS") (pintype "power_in"))
      (node (ref "CON2") (pin "B4,A9:VBUS") (pinfunction "VBUS_B4,A9:VBUS") (pintype "power_in"))
      (node (ref "F1") (pin "1") (pinfunction "1_1") (pintype "bidirectional"))
    )
    (net (code "52") (name "/VRGE_AVDD") (class "Default")
      (node (ref "C25") (pin "2") (pinfunction "2_2") (pintype "passive"))
      (node (ref "R28") (pin "1") (pinfunction "1_1") (pintype "bidirectional"))
      (node (ref "U1") (pin "46") (pinfunction "46:VRGE_AVDD_46") (pintype "power_in"))
    )
    (net (code "53") (name "/VRGE_LV") (class "Default")
      (node (ref "L2") (pin "1") (pinfunction "2_1") (pintype "passive"))
      (node (ref "U1") (pin "48") (pinfunction "48:VRGE_LX_48") (pintype "output"))
    )
    (net (code "54") (name "/VSYS") (class "Default")
      (node (ref "C11") (pin "2") (pinfunction "2_2") (pintype "passive"))
      (node (ref "C12") (pin "2") (pinfunction "2_2") (pintype "passive"))
      (node (ref "C33") (pin "2") (pinfunction "2_2") (pintype "passive"))
      (node (ref "C34") (pin "2") (pinfunction "2_2") (pintype "passive"))
      (node (ref "CON3") (pin "VCC") (pinfunction "VCC_VCC") (pintype "bidirectional"))
      (node (ref "D2") (pin "1") (pinfunction "CATHODE_1") (pintype "passive"))
      (node (ref "D4") (pin "6") (pinfunction "VOUT_6") (pintype "bidirectional"))
      (node (ref "LED2") (pin "1-VDD") (pinfunction "VDD_1-VDD") (pintype "bidirectional"))
      (node (ref "R37") (pin "2") (pinfunction "2_2") (pintype "bidirectional"))
      (node (ref "R40") (pin "2") (pinfunction "2_2") (pintype "bidirectional"))
      (node (ref "R7") (pin "2") (pinfunction "2_2") (pintype "bidirectional"))
      (node (ref "U3") (pin "14") (pinfunction "VCCB_14") (pintype "power_in"))
      (node (ref "U4") (pin "5") (pinfunction "5:VIN_5") (pintype "power_in"))
      (node (ref "U4") (pin "8") (pinfunction "8:VINA_8") (pintype "input"))
      (node (ref "U6") (pin "15") (pinfunction "15:VREF_15") (pintype "input"))
      (node (ref "U6") (pin "16") (pinfunction "16:VDD_16") (pintype "power_in"))
    )
    (net (code "55") (name "/VSYS_3V3") (class "Default")
      (node (ref "C13") (pin "2") (pinfunction "2_2") (pintype "passive"))
      (node (ref "C15") (pin "2") (pinfunction "2_2") (pintype "passive"))
      (node (ref "C16") (pin "2") (pinfunction "2_2") (pintype "passive"))
      (node (ref "C17") (pin "2") (pinfunction "2_2") (pintype "passive"))
      (node (ref "C18") (pin "2") (pinfunction "2_2") (pintype "passive"))
      (node (ref "C19") (pin "2") (pinfunction "2_2") (pintype "passive"))
      (node (ref "C20") (pin "2") (pinfunction "2_2") (pintype "passive"))
      (node (ref "C21") (pin "2") (pinfunction "2_2") (pintype "passive"))
      (node (ref "C27") (pin "2") (pinfunction "2_2") (pintype "passive"))
      (node (ref "C28") (pin "2") (pinfunction "2_2") (pintype "passive"))
      (node (ref "C29") (pin "2") (pinfunction "2_2") (pintype "passive"))
      (node (ref "C3") (pin "2") (pinfunction "2_2") (pintype "passive"))
      (node (ref "C6") (pin "2") (pinfunction "2_2") (pintype "passive"))
      (node (ref "C7") (pin "2") (pinfunction "2_2") (pintype "passive"))
      (node (ref "D1") (pin "CATHODE") (pinfunction "CATHODE_CATHODE") (pintype "bidirectional"))
      (node (ref "R10") (pin "2") (pinfunction "2_2") (pintype "bidirectional"))
      (node (ref "R13") (pin "2") (pinfunction "2_2") (pintype "bidirectional"))
      (node (ref "R26") (pin "2") (pinfunction "2_2") (pintype "bidirectional"))
      (node (ref "R28") (pin "2") (pinfunction "2_2") (pintype "bidirectional"))
      (node (ref "R30") (pin "2") (pinfunction "2_2") (pintype "bidirectional"))
      (node (ref "R34") (pin "2") (pinfunction "2_2") (pintype "bidirectional"))
      (node (ref "R9") (pin "2") (pinfunction "2_2") (pintype "bidirectional"))
      (node (ref "U1") (pin "1") (pinfunction "1:IOVDD_1") (pintype "power_in"))
      (node (ref "U1") (pin "11") (pinfunction "11:IOVDD_11") (pintype "power_in"))
      (node (ref "U1") (pin "20") (pinfunction "20:IOVDD_20") (pintype "power_in"))
      (node (ref "U1") (pin "30") (pinfunction "30:IOVDD_30") (pintype "power_in"))
      (node (ref "U1") (pin "38") (pinfunction "38:IOVDD_38") (pintype "power_in"))
      (node (ref "U1") (pin "45") (pinfunction "45:IOVDD_45") (pintype "power_in"))
      (node (ref "U1") (pin "49") (pinfunction "49:VRGE_VIN_49") (pintype "input"))
      (node (ref "U1") (pin "53") (pinfunction "53:USB_DTP_VDD_53") (pintype "power_in"))
      (node (ref "U1") (pin "54") (pinfunction "54:QSPI_IOVDD_54") (pintype "power_in"))
      (node (ref "U2") (pin "8") (pinfunction "8:VCC_8") (pintype "power_in"))
      (node (ref "U3") (pin "1") (pinfunction "VCCA_1") (pintype "power_in"))
      (node (ref "U4") (pin "1") (pinfunction "1:VOUT_1") (pintype "power_in"))
      (node (ref "U4") (pin "10") (pinfunction "10:FB_10") (pintype "input"))
      (node (ref "U5") (pin "G") (pinfunction "1:GATE_G") (pintype "passive"))
      (node (ref "U7") (pin "22") (pinfunction "VDD_22") (pintype "bidirectional"))
      (node (ref "U7") (pin "25") (pinfunction "VBAT_25") (pintype "bidirectional"))
    )
    (net (code "56") (name "/XOUT") (class "Default")
      (node (ref "R31") (pin "1") (pinfunction "1_1") (pintype "bidirectional"))
      (node (ref "U1") (pin "22") (pinfunction "22:XOUT_22") (pintype "output"))
    )
    (net (code "57") (name "5V") (class "Default")
      (node (ref "C35") (pin "2") (pinfunction "2_2") (pintype "passive"))
      (node (ref "CON1") (pin "2") (pinfunction "2:5V_POWER_2") (pintype "power_in"))
      (node (ref "D4") (pin "1") (pinfunction "VIN_1") (pintype "bidirectional"))
    )
    (net (code "58") (name "GND") (class "Default")
      (node (ref "BT1") (pin "A") (pinfunction "A_A") (pintype "passive"))
      (node (ref "BT1") (pin "B") (pinfunction "B_B") (pintype "passive"))
      (node (ref "BT2") (pin "C") (pinfunction "C_C") (pintype "passive"))
      (node (ref "BT2") (pin "D") (pinfunction "D_D") (pintype "passive"))
      (node (ref "C1") (pin "1") (pinfunction "1_1") (pintype "passive"))
      (node (ref "C10") (pin "1") (pinfunction "1_1") (pintype "passive"))
      (node (ref "C11") (pin "1") (pinfunction "1_1") (pintype "passive"))
      (node (ref "C12") (pin "1") (pinfunction "1_1") (pintype "passive"))
      (node (ref "C13") (pin "1") (pinfunction "1_1") (pintype "passive"))
      (node (ref "C14") (pin "1") (pinfunction "1_1") (pintype "passive"))
      (node (ref "C15") (pin "1") (pinfunction "1_1") (pintype "passive"))
      (node (ref "C16") (pin "1") (pinfunction "1_1") (pintype "passive"))
      (node (ref "C17") (pin "1") (pinfunction "1_1") (pintype "passive"))
      (node (ref "C18") (pin "1") (pinfunction "1_1") (pintype "passive"))
      (node (ref "C19") (pin "1") (pinfunction "1_1") (pintype "passive"))
      (node (ref "C2") (pin "1") (pinfunction "1_1") (pintype "passive"))
      (node (ref "C20") (pin "1") (pinfunction "1_1") (pintype "passive"))
      (node (ref "C21") (pin "1") (pinfunction "1_1") (pintype "passive"))
      (node (ref "C22") (pin "1") (pinfunction "1_1") (pintype "passive"))
      (node (ref "C23") (pin "1") (pinfunction "1_1") (pintype "passive"))
      (node (ref "C24") (pin "1") (pinfunction "1_1") (pintype "passive"))
      (node (ref "C25") (pin "1") (pinfunction "1_1") (pintype "passive"))
      (node (ref "C26") (pin "1") (pinfunction "1_1") (pintype "passive"))
      (node (ref "C27") (pin "1") (pinfunction "1_1") (pintype "passive"))
      (node (ref "C28") (pin "1") (pinfunction "1_1") (pintype "passive"))
      (node (ref "C29") (pin "1") (pinfunction "1_1") (pintype "passive"))
      (node (ref "C3") (pin "1") (pinfunction "1_1") (pintype "passive"))
      (node (ref "C30") (pin "1") (pinfunction "1_1") (pintype "passive"))
      (node (ref "C31") (pin "1") (pinfunction "1_1") (pintype "passive"))
      (node (ref "C32") (pin "1") (pinfunction "1_1") (pintype "passive"))
      (node (ref "C33") (pin "1") (pinfunction "1_1") (pintype "passive"))
      (node (ref "C34") (pin "1") (pinfunction "1_1") (pintype "passive"))
      (node (ref "C35") (pin "1") (pinfunction "1_1") (pintype "passive"))
      (node (ref "C6") (pin "1") (pinfunction "1_1") (pintype "passive"))
      (node (ref "C7") (pin "1") (pinfunction "1_1") (pintype "passive"))
      (node (ref "C8") (pin "1") (pinfunction "1_1") (pintype "passive"))
      (node (ref "C9") (pin "1") (pinfunction "1_1") (pintype "passive"))
      (node (ref "CN1") (pin "2") (pinfunction "2_2") (pintype "bidirectional"))
      (node (ref "CN6") (pin "1") (pinfunction "1_1") (pintype "bidirectional"))
      (node (ref "CON1") (pin "14") (pinfunction "14:GND_14") (pintype "power_in"))
      (node (ref "CON1") (pin "20") (pinfunction "20:GND_20") (pintype "power_in"))
      (node (ref "CON1") (pin "25") (pinfunction "25:GND_25") (pintype "power_in"))
      (node (ref "CON1") (pin "30") (pinfunction "30:GND_30") (pintype "power_in"))
      (node (ref "CON1") (pin "34") (pinfunction "34:GND_34") (pintype "power_in"))
      (node (ref "CON1") (pin "39") (pinfunction "39:GND_39") (pintype "power_in"))
      (node (ref "CON1") (pin "9") (pinfunction "9:GND_9") (pintype "power_in"))
      (node (ref "CON2") (pin "A1,B12:GND") (pinfunction "GND_A1,B12:GND") (pintype "power_in"))
      (node (ref "CON2") (pin "B1,A12:GND") (pinfunction "GND_B1,A12:GND") (pintype "power_in"))
      (node (ref "CON2") (pin "SHILED1") (pinfunction "SHILED1_SHILED1") (pintype "bidirectional"))
      (node (ref "CON2") (pin "SHILED2") (pinfunction "SHILED2_SHILED2") (pintype "bidirectional"))
      (node (ref "CON2") (pin "SHILED3") (pinfunction "SHILED3_SHILED3") (pintype "bidirectional"))
      (node (ref "CON2") (pin "SHILED4") (pinfunction "SHILED4_SHILED4") (pintype "bidirectional"))
      (node (ref "CON2") (pin "SHILED5") (pinfunction "SHILED1_SHILED5") (pintype "bidirectional"))
      (node (ref "CON2") (pin "SHILED6") (pinfunction "SHILED2_SHILED6") (pintype "bidirectional"))
      (node (ref "CON2") (pin "SHILED7") (pinfunction "SHILED3_SHILED7") (pintype "bidirectional"))
      (node (ref "CON2") (pin "SHILED8") (pinfunction "SHILED4_SHILED8") (pintype "bidirectional"))
      (node (ref "CON3") (pin "GND") (pinfunction "GND_GND") (pintype "bidirectional"))
      (node (ref "D4") (pin "2") (pinfunction "GND_2") (pintype "bidirectional"))
      (node (ref "D4") (pin "3") (pinfunction "CE_3") (pintype "bidirectional"))
      (node (ref "LED1") (pin "CATHODE") (pinfunction "CATHODE_CATHODE") (pintype "passive"))
      (node (ref "LED2") (pin "3-VSS") (pinfunction "VSS_3-VSS") (pintype "bidirectional"))
      (node (ref "OSC") (pin "2") (pinfunction "#2_2") (pintype "power_in"))
      (node (ref "OSC") (pin "4") (pinfunction "#4_4") (pintype "power_in"))
      (node (ref "R1") (pin "2") (pinfunction "2_2") (pintype "bidirectional"))
      (node (ref "R15") (pin "1") (pinfunction "1_1") (pintype "bidirectional"))
      (node (ref "R2") (pin "2") (pinfunction "2_2") (pintype "bidirectional"))
      (node (ref "R35") (pin "1") (pinfunction "1_1") (pintype "bidirectional"))
      (node (ref "R38") (pin "1") (pinfunction "1_1") (pintype "bidirectional"))
      (node (ref "R6") (pin "1") (pinfunction "1_1") (pintype "bidirectional"))
      (node (ref "R8") (pin "1") (pinfunction "1_1") (pintype "bidirectional"))
      (node (ref "U1") (pin "47") (pinfunction "47:VREG_PGND_47") (pintype "power_in"))
      (node (ref "U1") (pin "61") (pinfunction "61:GND_61") (pintype "power_in"))
      (node (ref "U1") (pin "P$62") (pinfunction "61:GND_P$62") (pintype "power_in"))
      (node (ref "U1") (pin "P$63") (pinfunction "61:GND_P$63") (pintype "power_in"))
      (node (ref "U1") (pin "P$64") (pinfunction "61:GND_P$64") (pintype "power_in"))
      (node (ref "U1") (pin "P$65") (pinfunction "61:GND_P$65") (pintype "power_in"))
      (node (ref "U1") (pin "P$66") (pinfunction "61:GND_P$66") (pintype "power_in"))
      (node (ref "U1") (pin "P$67") (pinfunction "61:GND_P$67") (pintype "power_in"))
      (node (ref "U1") (pin "P$68") (pinfunction "61:GND_P$68") (pintype "power_in"))
      (node (ref "U1") (pin "P$69") (pinfunction "61:GND_P$69") (pintype "power_in"))
      (node (ref "U1") (pin "P$70") (pinfunction "61:GND_P$70") (pintype "power_in"))
      (node (ref "U2") (pin "4") (pinfunction "4:VSS_4") (pintype "power_in"))
      (node (ref "U2") (pin "9") (pinfunction "4:VSS_9") (pintype "power_in"))
      (node (ref "U3") (pin "7") (pinfunction "GND_7") (pintype "power_in"))
      (node (ref "U4") (pin "3") (pinfunction "3:GND_3") (pintype "power_in"))
      (node (ref "U4") (pin "9") (pinfunction "9:GND_9") (pintype "power_in"))
      (node (ref "U4") (pin "PAD") (pinfunction "3:GND_PAD") (pintype "power_in"))
      (node (ref "U6") (pin "14") (pinfunction "14:AGND_14") (pintype "power_in"))
      (node (ref "U6") (pin "9") (pinfunction "9:DGND_9") (pintype "power_in"))
      (node (ref "U7") (pin "10") (pinfunction "D3_10") (pintype "bidirectional"))
      (node (ref "U7") (pin "14") (pinfunction "E/RD#_14") (pintype "bidirectional"))
      (node (ref "U7") (pin "15") (pinfunction "R/W#_15") (pintype "bidirectional"))
      (node (ref "U7") (pin "16") (pinfunction "D/C#_16") (pintype "bidirectional"))
      (node (ref "U7") (pin "18") (pinfunction "CS#_18") (pintype "bidirectional"))
      (node (ref "U7") (pin "19") (pinfunction "BS2_19") (pintype "bidirectional"))
      (node (ref "U7") (pin "2") (pinfunction "VLSS_2") (pintype "bidirectional"))
      (node (ref "U7") (pin "21") (pinfunction "BS0_21") (pintype "bidirectional"))
      (node (ref "U7") (pin "23") (pinfunction "VSS_23") (pintype "bidirectional"))
      (node (ref "U7") (pin "6") (pinfunction "D7_6") (pintype "bidirectional"))
      (node (ref "U7") (pin "7") (pinfunction "D6_7") (pintype "bidirectional"))
      (node (ref "U7") (pin "8") (pinfunction "D5_8") (pintype "bidirectional"))
      (node (ref "U7") (pin "9") (pinfunction "D4_9") (pintype "bidirectional"))
    )
    (net (code "59") (name "Net-(BT1-PadC)") (class "Default")
      (node (ref "BT1") (pin "C") (pinfunction "C_C") (pintype "passive"))
      (node (ref "BT1") (pin "D") (pinfunction "D_D") (pintype "passive"))
      (node (ref "R29") (pin "2") (pinfunction "2_2") (pintype "bidirectional"))
    )
    (net (code "60") (name "Net-(C10-Pad2)") (class "Default")
      (node (ref "C10") (pin "2") (pinfunction "2_2") (pintype "passive"))
      (node (ref "D1") (pin "ANODE") (pinfunction "ANODE_ANODE") (pintype "bidirectional"))
      (node (ref "R13") (pin "1") (pinfunction "1_1") (pintype "bidirectional"))
      (node (ref "R14") (pin "2") (pinfunction "2_2") (pintype "bidirectional"))
    )
    (net (code "61") (name "Net-(CN1-Pad1)") (class "Default")
      (node (ref "CN1") (pin "1") (pinfunction "1_1") (pintype "bidirectional"))
      (node (ref "R32") (pin "2") (pinfunction "2_2") (pintype "bidirectional"))
    )
    (net (code "62") (name "Net-(CN1-Pad3)") (class "Default")
      (node (ref "CN1") (pin "3") (pinfunction "3_3") (pintype "bidirectional"))
      (node (ref "R33") (pin "2") (pinfunction "2_2") (pintype "bidirectional"))
    )
    (net (code "63") (name "Net-(CON2-CC1)") (class "Default")
      (node (ref "CON2") (pin "A5:CC1") (pinfunction "CC1_A5:CC1") (pintype "bidirectional"))
      (node (ref "R1") (pin "1") (pinfunction "1_1") (pintype "bidirectional"))
    )
    (net (code "64") (name "Net-(CON2-CC2)") (class "Default")
      (node (ref "CON2") (pin "B5:CC2") (pinfunction "CC2_B5:CC2") (pintype "bidirectional"))
      (node (ref "R2") (pin "1") (pinfunction "1_1") (pintype "bidirectional"))
    )
    (net (code "65") (name "Net-(CON2-DN1)") (class "Default")
      (node (ref "CON2") (pin "A7:DN1") (pinfunction "DN1_A7:DN1") (pintype "bidirectional"))
      (node (ref "CON2") (pin "B7:DN2") (pinfunction "DN2_B7:DN2") (pintype "bidirectional"))
      (node (ref "R3") (pin "1") (pinfunction "1_1") (pintype "bidirectional"))
    )
    (net (code "66") (name "Net-(D2-ANODE)") (class "Default")
      (node (ref "D2") (pin "2") (pinfunction "ANODE_2") (pintype "passive"))
      (node (ref "F1") (pin "2") (pinfunction "2_2") (pintype "bidirectional"))
      (node (ref "R5") (pin "2") (pinfunction "2_2") (pintype "bidirectional"))
    )
    (net (code "67") (name "Net-(D4-ST)") (class "Default")
      (node (ref "D4") (pin "5") (pinfunction "ST_5") (pintype "bidirectional"))
      (node (ref "R40") (pin "1") (pinfunction "1_1") (pintype "bidirectional"))
    )
    (net (code "68") (name "Net-(LED1-PadANODE)") (class "Default")
      (node (ref "LED1") (pin "ANODE") (pinfunction "ANODE_ANODE") (pintype "passive"))
      (node (ref "R36") (pin "1") (pinfunction "1_1") (pintype "bidirectional"))
    )
    (net (code "69") (name "Net-(U1-24:SWCLK)") (class "Default")
      (node (ref "R32") (pin "1") (pinfunction "1_1") (pintype "bidirectional"))
      (node (ref "U1") (pin "24") (pinfunction "24:SWCLK_24") (pintype "bidirectional"))
    )
    (net (code "70") (name "Net-(U1-25:SWD)") (class "Default")
      (node (ref "R33") (pin "1") (pinfunction "1_1") (pintype "bidirectional"))
      (node (ref "U1") (pin "25") (pinfunction "25:SWD_25") (pintype "bidirectional"))
    )
    (net (code "71") (name "Net-(U1-44:ADC_AVDD)") (class "Default")
      (node (ref "C14") (pin "2") (pinfunction "2_2") (pintype "passive"))
      (node (ref "R27") (pin "1") (pinfunction "1_1") (pintype "bidirectional"))
      (node (ref "U1") (pin "44") (pinfunction "44:ADC_AVDD_44") (pintype "power_in"))
    )
    (net (code "72") (name "Net-(U4-2:LX2)") (class "Default")
      (node (ref "L1") (pin "2") (pinfunction "2_2") (pintype "bidirectional"))
      (node (ref "U4") (pin "2") (pinfunction "2:LX2_2") (pintype "input"))
    )
    (net (code "73") (name "Net-(U4-4:LX1)") (class "Default")
      (node (ref "L1") (pin "1") (pinfunction "1_1") (pintype "bidirectional"))
      (node (ref "U4") (pin "4") (pinfunction "4:LX1_4") (pintype "output"))
    )
    (net (code "74") (name "Net-(U4-6:EN)") (class "Default")
      (node (ref "R7") (pin "1") (pinfunction "1_1") (pintype "bidirectional"))
      (node (ref "U4") (pin "6") (pinfunction "6:EN_6") (pintype "input"))
    )
    (net (code "75") (name "Net-(U5-3:DRAIN)") (class "Default")
      (node (ref "C32") (pin "2") (pinfunction "2_2") (pintype "passive"))
      (node (ref "R37") (pin "1") (pinfunction "1_1") (pintype "bidirectional"))
      (node (ref "R38") (pin "2") (pinfunction "2_2") (pintype "bidirectional"))
      (node (ref "U5") (pin "D") (pinfunction "3:DRAIN_D") (pintype "passive"))
    )
    (net (code "76") (name "Net-(U6-1:CH0)") (class "Default")
      (node (ref "R23") (pin "2") (pinfunction "2_2") (pintype "bidirectional"))
      (node (ref "U6") (pin "1") (pinfunction "1:CH0_1") (pintype "input"))
    )
    (net (code "77") (name "Net-(U6-2:CH1)") (class "Default")
      (node (ref "R22") (pin "2") (pinfunction "2_2") (pintype "bidirectional"))
      (node (ref "U6") (pin "2") (pinfunction "2:CH1_2") (pintype "input"))
    )
    (net (code "78") (name "Net-(U6-3:CH2)") (class "Default")
      (node (ref "R21") (pin "2") (pinfunction "2_2") (pintype "bidirectional"))
      (node (ref "U6") (pin "3") (pinfunction "3:CH2_3") (pintype "input"))
    )
    (net (code "79") (name "Net-(U6-4:CH3)") (class "Default")
      (node (ref "R20") (pin "2") (pinfunction "2_2") (pintype "bidirectional"))
      (node (ref "U6") (pin "4") (pinfunction "4:CH3_4") (pintype "input"))
    )
    (net (code "80") (name "Net-(U6-5:CH4)") (class "Default")
      (node (ref "R19") (pin "2") (pinfunction "2_2") (pintype "bidirectional"))
      (node (ref "U6") (pin "5") (pinfunction "5:CH4_5") (pintype "input"))
    )
    (net (code "81") (name "Net-(U6-6:CH5)") (class "Default")
      (node (ref "R18") (pin "2") (pinfunction "2_2") (pintype "bidirectional"))
      (node (ref "U6") (pin "6") (pinfunction "6:CH5_6") (pintype "input"))
    )
    (net (code "82") (name "Net-(U6-7:CH6)") (class "Default")
      (node (ref "R17") (pin "2") (pinfunction "2_2") (pintype "bidirectional"))
      (node (ref "U6") (pin "7") (pinfunction "7:CH6_7") (pintype "input"))
    )
    (net (code "83") (name "Net-(U6-8:CH7)") (class "Default")
      (node (ref "R16") (pin "2") (pinfunction "2_2") (pintype "bidirectional"))
      (node (ref "U6") (pin "8") (pinfunction "8:CH7_8") (pintype "input"))
    )
    (net (code "84") (name "Net-(U7-BS1)") (class "Default")
      (node (ref "R14") (pin "1") (pinfunction "1_1") (pintype "bidirectional"))
      (node (ref "U7") (pin "17") (pinfunction "RES#_17") (pintype "bidirectional"))
      (node (ref "U7") (pin "20") (pinfunction "BS1_20") (pintype "bidirectional"))
    )
    (net (code "85") (name "Net-(U7-C1N)") (class "Default")
      (node (ref "C4") (pin "1") (pinfunction "1_1") (pintype "passive"))
      (node (ref "U7") (pin "26") (pinfunction "C1N_26") (pintype "bidirectional"))
    )
    (net (code "86") (name "Net-(U7-C1P)") (class "Default")
      (node (ref "C4") (pin "2") (pinfunction "2_2") (pintype "passive"))
      (node (ref "U7") (pin "27") (pinfunction "C1P_27") (pintype "bidirectional"))
    )
    (net (code "87") (name "Net-(U7-C2N)") (class "Default")
      (node (ref "C5") (pin "1") (pinfunction "1_1") (pintype "passive"))
      (node (ref "U7") (pin "28") (pinfunction "C2N_28") (pintype "bidirectional"))
    )
    (net (code "88") (name "Net-(U7-C2P)") (class "Default")
      (node (ref "C5") (pin "2") (pinfunction "2_2") (pintype "passive"))
      (node (ref "U7") (pin "29") (pinfunction "C2P_29") (pintype "bidirectional"))
    )
    (net (code "89") (name "Net-(U7-IREF)") (class "Default")
      (node (ref "R15") (pin "2") (pinfunction "2_2") (pintype "bidirectional"))
      (node (ref "U7") (pin "5") (pinfunction "IREF_5") (pintype "bidirectional"))
    )
    (net (code "90") (name "Net-(U7-VCC)") (class "Default")
      (node (ref "C9") (pin "2") (pinfunction "2_2") (pintype "passive"))
      (node (ref "U7") (pin "3") (pinfunction "VCC_3") (pintype "bidirectional"))
    )
    (net (code "91") (name "Net-(U7-VCOMH)") (class "Default")
      (node (ref "C8") (pin "2") (pinfunction "2_2") (pintype "passive"))
      (node (ref "U7") (pin "4") (pinfunction "VCOMH_4") (pintype "bidirectional"))
    )
    (net (code "92") (name "unconnected-(CON1-7:GPIO4(GPCLK0)-Pad7)") (class "Default")
      (node (ref "CON1") (pin "7") (pinfunction "7:GPIO4(GPCLK0)_7") (pintype "bidirectional"))
    )
    (net (code "93") (name "unconnected-(CON1-12:GPIO18(GPIO_GEN1,PCM_CLK)-Pad12)") (class "Default")
      (node (ref "CON1") (pin "12") (pinfunction "12:GPIO18(GPIO_GEN1,PCM_CLK)_12") (pintype "bidirectional"))
    )
    (net (code "94") (name "unconnected-(CON1-16:GPIO23(GPIO_GEN4)-Pad16)") (class "Default")
      (node (ref "CON1") (pin "16") (pinfunction "16:GPIO23(GPIO_GEN4)_16") (pintype "bidirectional"))
    )
    (net (code "95") (name "unconnected-(CON1-18:GPIO24(GPIO_GEN5)-Pad18)") (class "Default")
      (node (ref "CON1") (pin "18") (pinfunction "18:GPIO24(GPIO_GEN5)_18") (pintype "bidirectional"))
    )
    (net (code "96") (name "unconnected-(CON1-19:GPIO10(SPI_MOSI)-Pad19)") (class "Default")
      (node (ref "CON1") (pin "19") (pinfunction "19:GPIO10(SPI_MOSI)_19") (pintype "bidirectional"))
    )
    (net (code "97") (name "unconnected-(CON1-21:GPIO9(SPI_MISO)-Pad21)") (class "Default")
      (node (ref "CON1") (pin "21") (pinfunction "21:GPIO9(SPI_MISO)_21") (pintype "bidirectional"))
    )
    (net (code "98") (name "unconnected-(CON1-22:GPIO25(GPIO_GEN6)-Pad22)") (class "Default")
      (node (ref "CON1") (pin "22") (pinfunction "22:GPIO25(GPIO_GEN6)_22") (pintype "bidirectional"))
    )
    (net (code "99") (name "unconnected-(CON1-23:GPIO11(SPI_CLK)-Pad23)") (class "Default")
      (node (ref "CON1") (pin "23") (pinfunction "23:GPIO11(SPI_CLK)_23") (pintype "bidirectional"))
    )
    (net (code "100") (name "unconnected-(CON1-24:GPIO8(SPI_CE0_N)-Pad24)") (class "Default")
      (node (ref "CON1") (pin "24") (pinfunction "24:GPIO8(SPI_CE0_N)_24") (pintype "bidirectional"))
    )
    (net (code "101") (name "unconnected-(CON1-26:GPIO7(SPI_CE1_N)-Pad26)") (class "Default")
      (node (ref "CON1") (pin "26") (pinfunction "26:GPIO7(SPI_CE1_N)_26") (pintype "bidirectional"))
    )
    (net (code "102") (name "unconnected-(CON1-27:GPIO0(I2C,EEPROM_SDA)-Pad27)") (class "Default")
      (node (ref "CON1") (pin "27") (pinfunction "27:GPIO0(I2C,EEPROM_SDA)_27") (pintype "bidirectional"))
    )
    (net (code "103") (name "unconnected-(CON1-28:GPIO1(I2C,EEPROM_SCL)-Pad28)") (class "Default")
      (node (ref "CON1") (pin "28") (pinfunction "28:GPIO1(I2C,EEPROM_SCL)_28") (pintype "bidirectional"))
    )
    (net (code "104") (name "unconnected-(CON1-32:GPIO12(PWM0)-Pad32)") (class "Default")
      (node (ref "CON1") (pin "32") (pinfunction "32:GPIO12(PWM0)_32") (pintype "bidirectional"))
    )
    (net (code "105") (name "unconnected-(CON1-36:GPIO16-Pad36)") (class "Default")
      (node (ref "CON1") (pin "36") (pinfunction "36:GPIO16_36") (pintype "bidirectional"))
    )
    (net (code "106") (name "unconnected-(CON1-38:GPIO20(PCM_DIN)-Pad38)") (class "Default")
      (node (ref "CON1") (pin "38") (pinfunction "38:GPIO20(PCM_DIN)_38") (pintype "bidirectional"))
    )
    (net (code "107") (name "unconnected-(CON1-40:GPIO21(PCM_DOUT)-Pad40)") (class "Default")
      (node (ref "CON1") (pin "40") (pinfunction "40:GPIO21(PCM_DOUT)_40") (pintype "bidirectional"))
    )
    (net (code "108") (name "unconnected-(CON2-SBU1-PadA8:SBU1)") (class "Default")
      (node (ref "CON2") (pin "A8:SBU1") (pinfunction "SBU1_A8:SBU1") (pintype "bidirectional"))
    )
    (net (code "109") (name "unconnected-(CON2-SBU2-PadB8:SBU2)") (class "Default")
      (node (ref "CON2") (pin "B8:SBU2") (pinfunction "SBU2_B8:SBU2") (pintype "bidirectional"))
    )
    (net (code "110") (name "unconnected-(D4-NC-Pad4)") (class "Default")
      (node (ref "D4") (pin "4") (pinfunction "NC_4") (pintype "bidirectional"))
    )
    (net (code "111") (name "unconnected-(LED2-DOUT-Pad2-DOUT)") (class "Default")
      (node (ref "LED2") (pin "2-DOUT") (pinfunction "DOUT_2-DOUT") (pintype "bidirectional"))
    )
    (net (code "112") (name "unconnected-(U1-9:GPIO06-Pad9)") (class "Default")
      (node (ref "U1") (pin "9") (pinfunction "9:GPIO06_9") (pintype "bidirectional"))
    )
    (net (code "113") (name "unconnected-(U1-10:GPIO07-Pad10)") (class "Default")
      (node (ref "U1") (pin "10") (pinfunction "10:GPIO07_10") (pintype "bidirectional"))
    )
    (net (code "114") (name "unconnected-(U1-12:GPIO08-Pad12)") (class "Default")
      (node (ref "U1") (pin "12") (pinfunction "12:GPIO08_12") (pintype "bidirectional"))
    )
    (net (code "115") (name "unconnected-(U1-13:GPIO09-Pad13)") (class "Default")
      (node (ref "U1") (pin "13") (pinfunction "13:GPIO09_13") (pintype "bidirectional"))
    )
    (net (code "116") (name "unconnected-(U1-15:GPIO11-Pad15)") (class "Default")
      (node (ref "U1") (pin "15") (pinfunction "15:GPIO11_15") (pintype "bidirectional"))
    )
    (net (code "117") (name "unconnected-(U1-17:GPIO13-Pad17)") (class "Default")
      (node (ref "U1") (pin "17") (pinfunction "17:GPIO13_17") (pintype "bidirectional"))
    )
    (net (code "118") (name "unconnected-(U1-18:GPIO14-Pad18)") (class "Default")
      (node (ref "U1") (pin "18") (pinfunction "18:GPIO14_18") (pintype "bidirectional"))
    )
    (net (code "119") (name "unconnected-(U1-19:GPIO15-Pad19)") (class "Default")
      (node (ref "U1") (pin "19") (pinfunction "19:GPIO15_19") (pintype "bidirectional"))
    )
    (net (code "120") (name "unconnected-(U1-29:GPIO18-Pad29)") (class "Default")
      (node (ref "U1") (pin "29") (pinfunction "29:GPIO18_29") (pintype "bidirectional"))
    )
    (net (code "121") (name "unconnected-(U1-32:GPIO20-Pad32)") (class "Default")
      (node (ref "U1") (pin "32") (pinfunction "32:GPIO20_32") (pintype "bidirectional"))
    )
    (net (code "122") (name "unconnected-(U1-33:GPIO21-Pad33)") (class "Default")
      (node (ref "U1") (pin "33") (pinfunction "33:GPIO21_33") (pintype "bidirectional"))
    )
    (net (code "123") (name "unconnected-(U1-40:GPIO26_ADC0-Pad40)") (class "Default")
      (node (ref "U1") (pin "40") (pinfunction "40:GPIO26_ADC0_40") (pintype "bidirectional"))
    )
    (net (code "124") (name "unconnected-(U1-41:GPIO27_ADC1-Pad41)") (class "Default")
      (node (ref "U1") (pin "41") (pinfunction "41:GPIO27_ADC1_41") (pintype "bidirectional"))
    )
    (net (code "125") (name "unconnected-(U1-42:GPIO28_ADC2-Pad42)") (class "Default")
      (node (ref "U1") (pin "42") (pinfunction "42:GPIO28_ADC2_42") (pintype "bidirectional"))
    )
    (net (code "126") (name "unconnected-(U3-NC1-Pad6)") (class "Default")
      (node (ref "U3") (pin "6") (pinfunction "NC1_6") (pintype "no_connect"))
    )
    (net (code "127") (name "unconnected-(U3-NC2-Pad9)") (class "Default")
      (node (ref "U3") (pin "9") (pinfunction "NC2_9") (pintype "no_connect"))
    )
    (net (code "128") (name "unconnected-(U7-NC-Pad1)") (class "Default")
      (node (ref "U7") (pin "1") (pinfunction "NC_1") (pintype "bidirectional"))
    )
    (net (code "129") (name "unconnected-(U7-NC-Pad24)") (class "Default")
      (node (ref "U7") (pin "24") (pinfunction "NC_24") (pintype "bidirectional"))
    )
    (net (code "130") (name "unconnected-(U7-NC-Pad30)") (class "Default")
      (node (ref "U7") (pin "30") (pinfunction "NC_30") (pintype "bidirectional"))
    )
  )
)
